# ACB-Lite_3_2.net
KiCad netlist of a schematic drawn in EAGLE
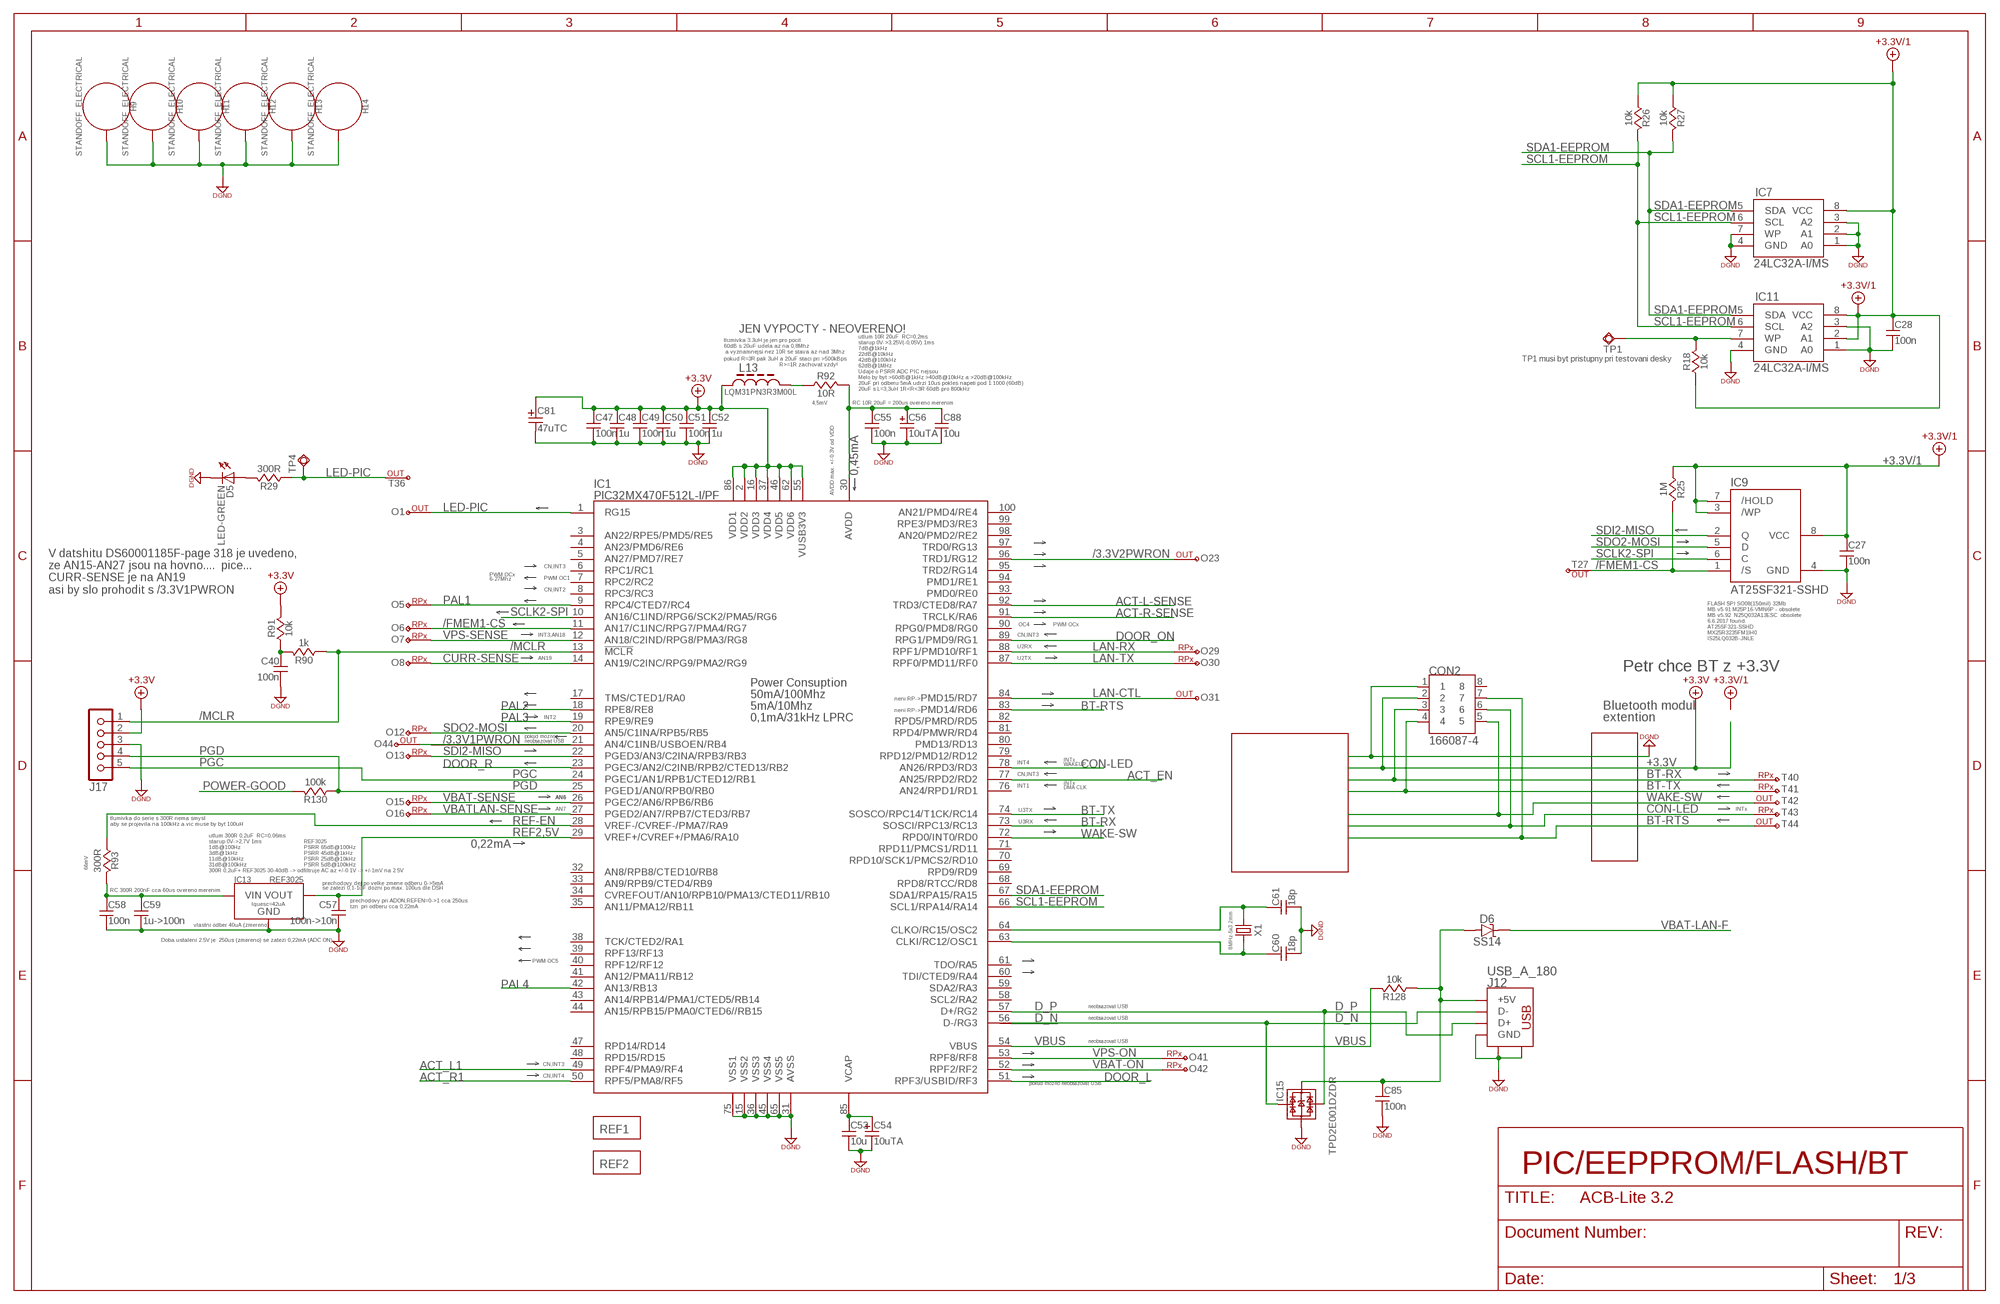
[diagram p0: schematic, sheet 1]
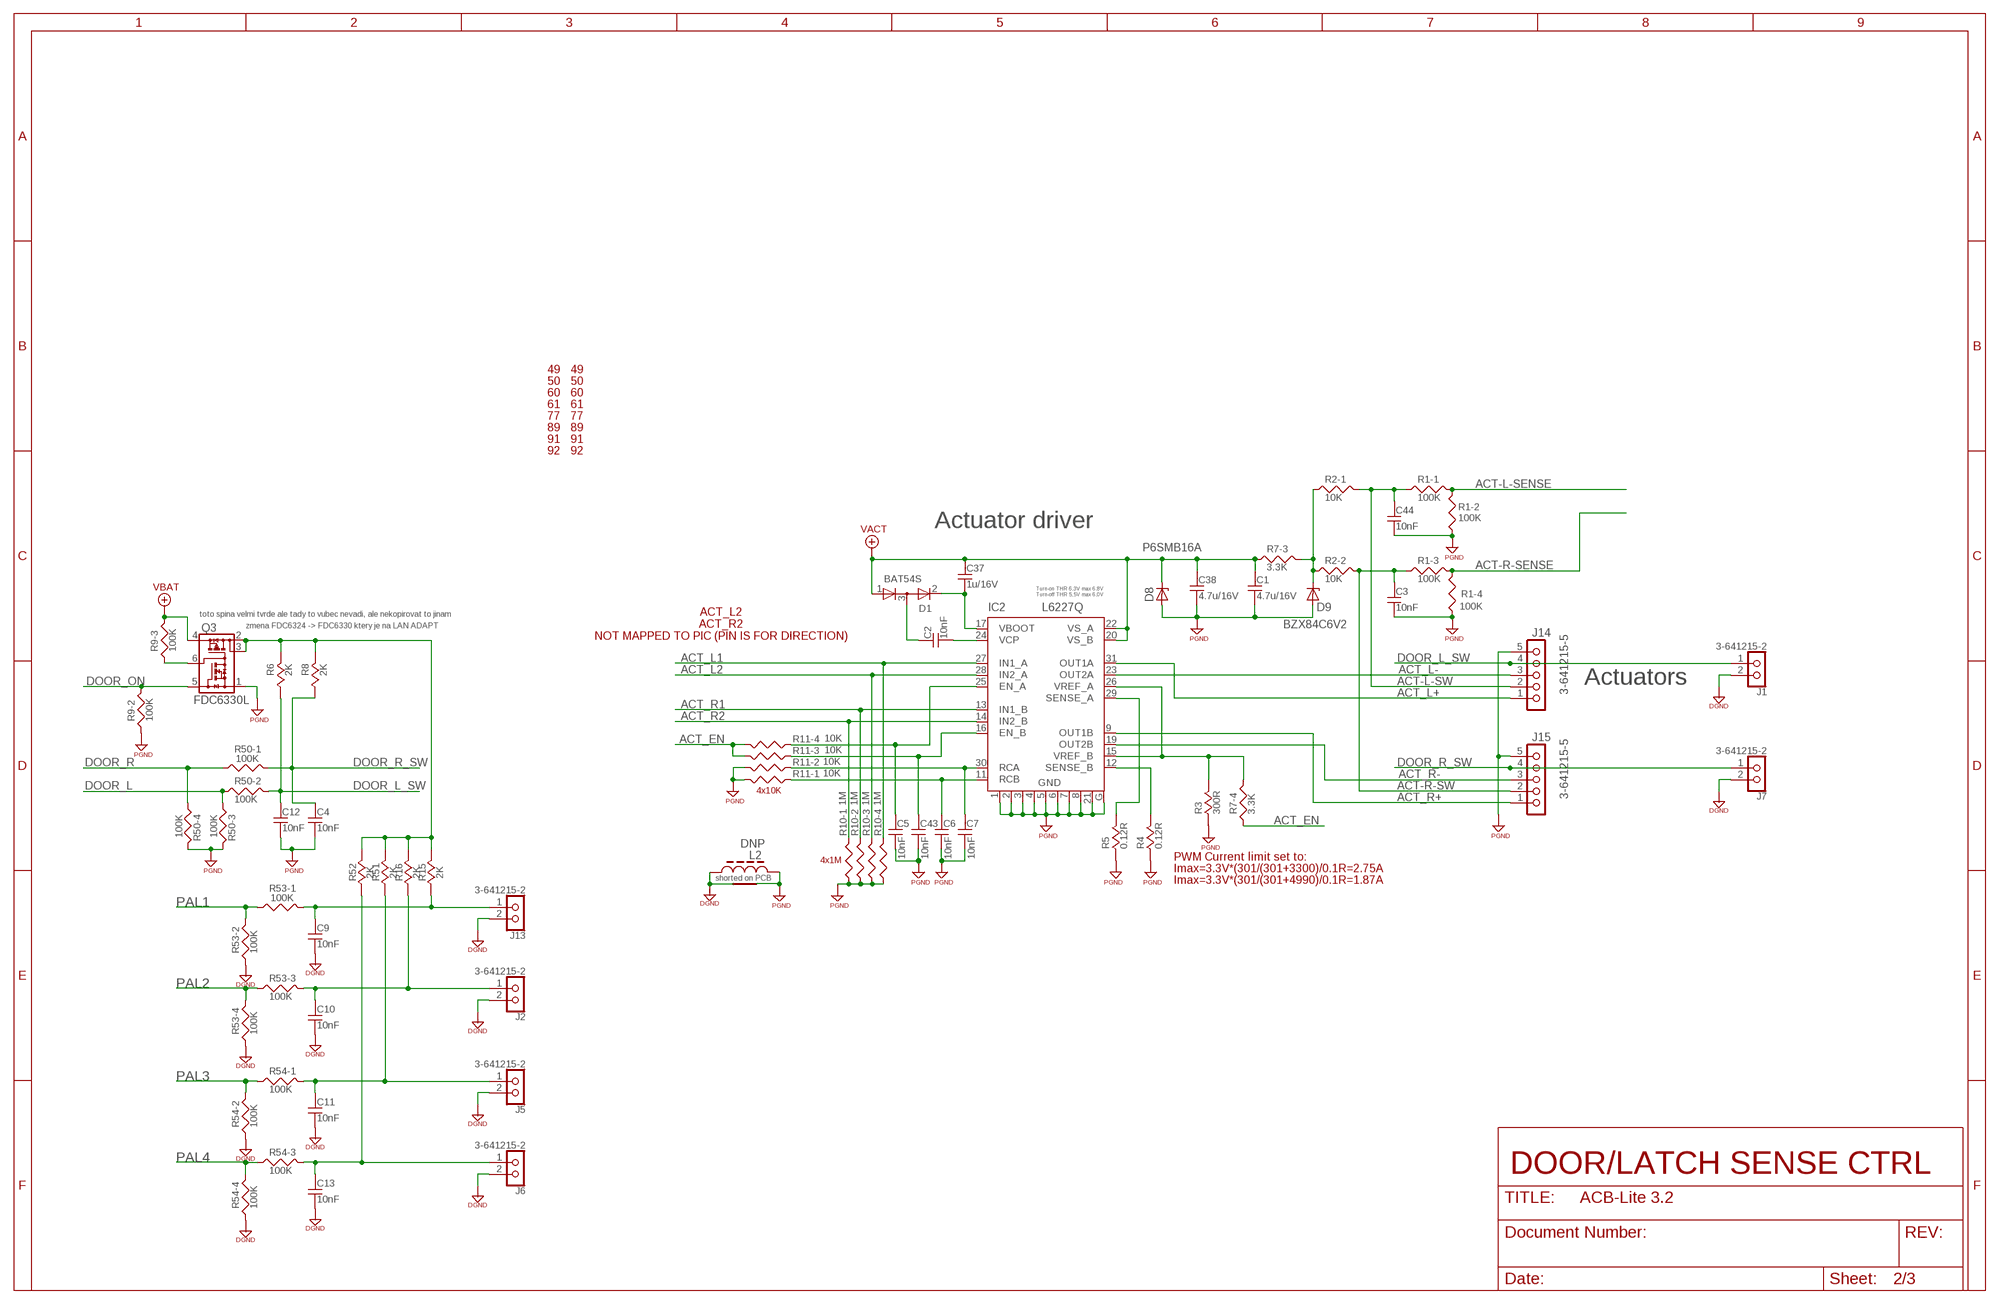
[diagram p1: schematic, sheet 2]
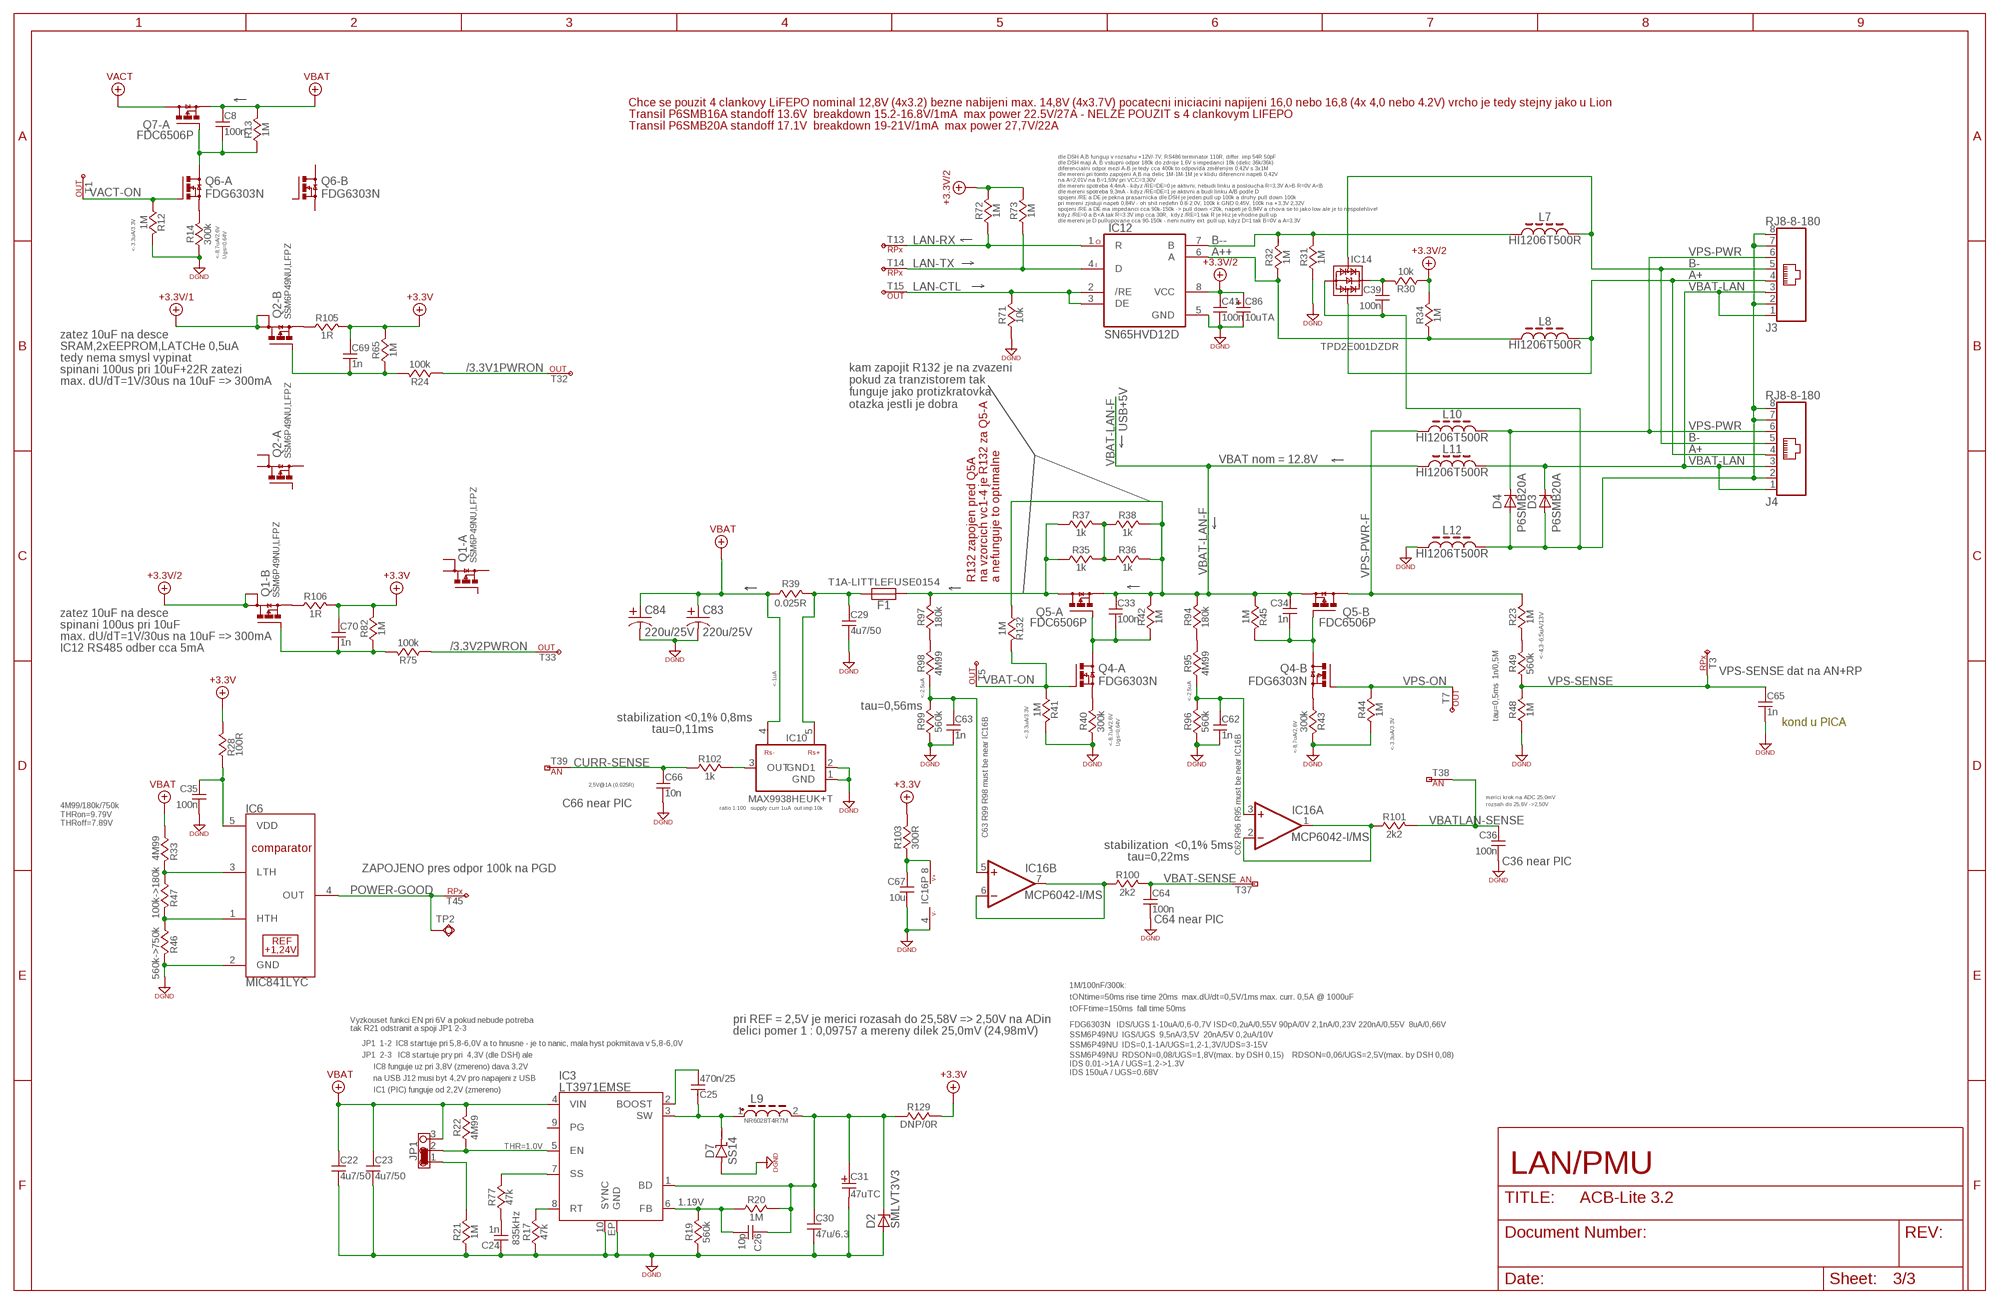
[diagram p2: schematic, sheet 3]

(export (version "E")
  (design (tool "Eeschema 10.0.6"))
  (components
    (comp (ref "C8")
      (value "100n")
      (footprint "eagle-import:0603")
      (libsource (lib "eagle-import") (part "C-0603"))
    )
    (comp (ref "C22")
      (value "4u7/50")
      (footprint "eagle-import:1206")
      (libsource (lib "eagle-import") (part "C-1206"))
    )
    (comp (ref "C23")
      (value "4u7/50")
      (footprint "eagle-import:1206")
      (libsource (lib "eagle-import") (part "C-1206"))
    )
    (comp (ref "C24")
      (value "1n")
      (footprint "eagle-import:0603")
      (libsource (lib "eagle-import") (part "C-0603"))
    )
    (comp (ref "C25")
      (value "470n/25")
      (footprint "eagle-import:0603")
      (libsource (lib "eagle-import") (part "C-0603"))
    )
    (comp (ref "C26")
      (value "10p")
      (footprint "eagle-import:0603")
      (libsource (lib "eagle-import") (part "C-0603"))
    )
    (comp (ref "C29")
      (value "4u7/50")
      (footprint "eagle-import:1206")
      (libsource (lib "eagle-import") (part "C-1206"))
    )
    (comp (ref "C30")
      (value "47u/6.3")
      (footprint "eagle-import:1206")
      (libsource (lib "eagle-import") (part "C-1206"))
    )
    (comp (ref "C31")
      (value "47uTC")
      (footprint "eagle-import:CT-C")
      (libsource (lib "eagle-import") (part "CT-C"))
    )
    (comp (ref "C33")
      (value "100n")
      (footprint "eagle-import:0603")
      (libsource (lib "eagle-import") (part "C-0603"))
    )
    (comp (ref "C34")
      (value "1n")
      (footprint "eagle-import:0603")
      (libsource (lib "eagle-import") (part "C-0603"))
    )
    (comp (ref "C35")
      (value "100n")
      (footprint "eagle-import:0603")
      (libsource (lib "eagle-import") (part "C-0603"))
    )
    (comp (ref "C36")
      (value "100n")
      (footprint "eagle-import:0603")
      (libsource (lib "eagle-import") (part "C-0603"))
    )
    (comp (ref "C39")
      (value "100n")
      (footprint "eagle-import:0603")
      (libsource (lib "eagle-import") (part "C-0603"))
    )
    (comp (ref "C41")
      (value "100n")
      (footprint "eagle-import:0603")
      (libsource (lib "eagle-import") (part "C-0603"))
    )
    (comp (ref "C62")
      (value "1n")
      (footprint "eagle-import:0603")
      (libsource (lib "eagle-import") (part "C-0603"))
    )
    (comp (ref "C63")
      (value "1n")
      (footprint "eagle-import:0603")
      (libsource (lib "eagle-import") (part "C-0603"))
    )
    (comp (ref "C64")
      (value "100n")
      (footprint "eagle-import:0603")
      (libsource (lib "eagle-import") (part "C-0603"))
    )
    (comp (ref "C65")
      (value "1n")
      (footprint "eagle-import:0603")
      (libsource (lib "eagle-import") (part "C-0603"))
    )
    (comp (ref "C66")
      (value "10n")
      (footprint "eagle-import:0603")
      (libsource (lib "eagle-import") (part "C-0603"))
    )
    (comp (ref "C67")
      (value "10u")
      (footprint "eagle-import:0603")
      (libsource (lib "eagle-import") (part "C-0603"))
    )
    (comp (ref "C69")
      (value "1n")
      (footprint "eagle-import:0603")
      (libsource (lib "eagle-import") (part "C-0603"))
    )
    (comp (ref "C70")
      (value "1n")
      (footprint "eagle-import:0603")
      (libsource (lib "eagle-import") (part "C-0603"))
    )
    (comp (ref "C83")
      (value "220u/25V")
      (footprint "eagle-import:CAP_8MM_DIA_SMT")
      (libsource (lib "eagle-import") (part "CAP-ELEC-SMD-8MM"))
    )
    (comp (ref "C84")
      (value "220u/25V")
      (footprint "eagle-import:CAP_8MM_DIA_SMT")
      (libsource (lib "eagle-import") (part "CAP-ELEC-SMD-8MM"))
    )
    (comp (ref "C86")
      (value "10uTA")
      (footprint "eagle-import:1206-POL-C")
      (libsource (lib "eagle-import") (part "CT-1206"))
    )
    (comp (ref "D2")
      (value "SMLVT3V3")
      (footprint "eagle-import:SMA")
      (libsource (lib "eagle-import") (part "SMLVT3V3"))
    )
    (comp (ref "D3")
      (value "P6SMB20A")
      (footprint "eagle-import:SMB")
      (libsource (lib "eagle-import") (part "P6SMB"))
    )
    (comp (ref "D4")
      (value "P6SMB20A")
      (footprint "eagle-import:SMB")
      (libsource (lib "eagle-import") (part "P6SMB"))
    )
    (comp (ref "D7")
      (value "SS14")
      (footprint "eagle-import:SMA")
      (libsource (lib "eagle-import") (part "DS-SMA"))
    )
    (comp (ref "F1")
      (value "T1A-LITTLEFUSE0154")
      (footprint "eagle-import:LITTLEFUSE0154")
      (libsource (lib "eagle-import") (part "POJISTKA-LITTLEFUSE0154"))
    )
    (comp (ref "IC3")
      (value "LT3971EMSE")
      (footprint "eagle-import:MSOP10EXP")
      (libsource (lib "eagle-import") (part "LT3971EMSE"))
    )
    (comp (ref "IC6")
      (value "MIC841LYC")
      (footprint "eagle-import:SC-70-5")
      (libsource (lib "eagle-import") (part "MIC841LYC"))
    )
    (comp (ref "IC10")
      (value "MAX9938HEUK+T")
      (footprint "eagle-import:SOT23-5")
      (libsource (lib "eagle-import") (part "TSM9938HEUK+T"))
    )
    (comp (ref "IC12")
      (value "SN65HVD12D")
      (footprint "eagle-import:SO08")
      (libsource (lib "eagle-import") (part "SN65HVD3082ED"))
    )
    (comp (ref "IC14")
      (value "TPD2E001DZDR")
      (footprint "eagle-import:SOT-143")
      (libsource (lib "eagle-import") (part "SR05.TCT"))
    )
    (comp (ref "IC16")
      (value "MCP6042-I/MS")
      (footprint "eagle-import:MSOP-08")
      (libsource (lib "eagle-import") (part "MCP6042-I/MS"))
    )
    (comp (ref "J3")
      (value "RJ8-8-180")
      (footprint "eagle-import:RJ8-8-180")
      (libsource (lib "eagle-import") (part "RJ8-8-180"))
    )
    (comp (ref "J4")
      (value "RJ8-8-180")
      (footprint "eagle-import:RJ8-8-180")
      (libsource (lib "eagle-import") (part "RJ8-8-180"))
    )
    (comp (ref "JP1")
      (value "JP3CLOSE12")
      (footprint "eagle-import:JP3CLOSE12")
      (libsource (lib "eagle-import") (part "JP3CLOSE12"))
    )
    (comp (ref "L7")
      (value "HI1206T500R")
      (footprint "eagle-import:1206")
      (libsource (lib "eagle-import") (part "L-1206"))
    )
    (comp (ref "L8")
      (value "HI1206T500R")
      (footprint "eagle-import:1206")
      (libsource (lib "eagle-import") (part "L-1206"))
    )
    (comp (ref "L9")
      (value "NR6028T4R7M")
      (footprint "eagle-import:NR6028")
      (libsource (lib "eagle-import") (part "NR6028"))
    )
    (comp (ref "L10")
      (value "HI1206T500R")
      (footprint "eagle-import:1206")
      (libsource (lib "eagle-import") (part "L-1206"))
    )
    (comp (ref "L11")
      (value "HI1206T500R")
      (footprint "eagle-import:1206")
      (libsource (lib "eagle-import") (part "L-1206"))
    )
    (comp (ref "L12")
      (value "HI1206T500R")
      (footprint "eagle-import:1206")
      (libsource (lib "eagle-import") (part "L-1206"))
    )
    (comp (ref "Q1")
      (value "SSM6P49NU,LFPZ")
      (footprint "eagle-import:MICRO_FET")
      (libsource (lib "eagle-import") (part "SSM6P49PZNU,LF"))
    )
    (comp (ref "Q2")
      (value "SSM6P49NU,LFPZ")
      (footprint "eagle-import:MICRO_FET")
      (libsource (lib "eagle-import") (part "SSM6P49PZNU,LF"))
    )
    (comp (ref "Q4")
      (value "FDG6303N")
      (footprint "eagle-import:SC70-6")
      (libsource (lib "eagle-import") (part "FDG6303N"))
    )
    (comp (ref "Q5")
      (value "FDC6506P")
      (footprint "eagle-import:SSOT-6")
      (libsource (lib "eagle-import") (part "FDC6506D"))
    )
    (comp (ref "Q6")
      (value "FDG6303N")
      (footprint "eagle-import:SC70-6")
      (libsource (lib "eagle-import") (part "FDG6303N"))
    )
    (comp (ref "Q7")
      (value "FDC6506P")
      (footprint "eagle-import:SSOT-6")
      (libsource (lib "eagle-import") (part "FDC6506D"))
    )
    (comp (ref "R12")
      (value "1M")
      (footprint "eagle-import:0603")
      (libsource (lib "eagle-import") (part "R-0603"))
    )
    (comp (ref "R13")
      (value "1M")
      (footprint "eagle-import:0603")
      (libsource (lib "eagle-import") (part "R-0603"))
    )
    (comp (ref "R14")
      (value "300k")
      (footprint "eagle-import:0603")
      (libsource (lib "eagle-import") (part "R-0603"))
    )
    (comp (ref "R17")
      (value "47k")
      (footprint "eagle-import:0603")
      (libsource (lib "eagle-import") (part "R-0603"))
    )
    (comp (ref "R19")
      (value "560k")
      (footprint "eagle-import:0603")
      (libsource (lib "eagle-import") (part "R-0603"))
    )
    (comp (ref "R20")
      (value "1M")
      (footprint "eagle-import:0603")
      (libsource (lib "eagle-import") (part "R-0603"))
    )
    (comp (ref "R21")
      (value "1M")
      (footprint "eagle-import:0603")
      (libsource (lib "eagle-import") (part "R-0603"))
    )
    (comp (ref "R22")
      (value "4M99")
      (footprint "eagle-import:0603")
      (libsource (lib "eagle-import") (part "R-0603"))
    )
    (comp (ref "R23")
      (value "1M")
      (footprint "eagle-import:0603")
      (libsource (lib "eagle-import") (part "R-0603"))
    )
    (comp (ref "R24")
      (value "100k")
      (footprint "eagle-import:0603")
      (libsource (lib "eagle-import") (part "R-0603"))
    )
    (comp (ref "R28")
      (value "100R")
      (footprint "eagle-import:0603")
      (libsource (lib "eagle-import") (part "R-0603"))
    )
    (comp (ref "R30")
      (value "10k")
      (footprint "eagle-import:0603")
      (libsource (lib "eagle-import") (part "R-0603"))
    )
    (comp (ref "R31")
      (value "1M")
      (footprint "eagle-import:0603")
      (libsource (lib "eagle-import") (part "R-0603"))
    )
    (comp (ref "R32")
      (value "1M")
      (footprint "eagle-import:0603")
      (libsource (lib "eagle-import") (part "R-0603"))
    )
    (comp (ref "R33")
      (value "4M99")
      (footprint "eagle-import:0603")
      (libsource (lib "eagle-import") (part "R-0603"))
    )
    (comp (ref "R34")
      (value "1M")
      (footprint "eagle-import:0603")
      (libsource (lib "eagle-import") (part "R-0603"))
    )
    (comp (ref "R35")
      (value "1k")
      (footprint "eagle-import:0805")
      (libsource (lib "eagle-import") (part "R-0805"))
    )
    (comp (ref "R36")
      (value "1k")
      (footprint "eagle-import:0805")
      (libsource (lib "eagle-import") (part "R-0805"))
    )
    (comp (ref "R37")
      (value "1k")
      (footprint "eagle-import:0805")
      (libsource (lib "eagle-import") (part "R-0805"))
    )
    (comp (ref "R38")
      (value "1k")
      (footprint "eagle-import:0805")
      (libsource (lib "eagle-import") (part "R-0805"))
    )
    (comp (ref "R39")
      (value "0.025R")
      (footprint "eagle-import:0805")
      (libsource (lib "eagle-import") (part "R-0805"))
    )
    (comp (ref "R40")
      (value "300k")
      (footprint "eagle-import:0603")
      (libsource (lib "eagle-import") (part "R-0603"))
    )
    (comp (ref "R41")
      (value "1M")
      (footprint "eagle-import:0603")
      (libsource (lib "eagle-import") (part "R-0603"))
    )
    (comp (ref "R42")
      (value "1M")
      (footprint "eagle-import:0603")
      (libsource (lib "eagle-import") (part "R-0603"))
    )
    (comp (ref "R43")
      (value "300k")
      (footprint "eagle-import:0603")
      (libsource (lib "eagle-import") (part "R-0603"))
    )
    (comp (ref "R44")
      (value "1M")
      (footprint "eagle-import:0603")
      (libsource (lib "eagle-import") (part "R-0603"))
    )
    (comp (ref "R45")
      (value "1M")
      (footprint "eagle-import:0603")
      (libsource (lib "eagle-import") (part "R-0603"))
    )
    (comp (ref "R46")
      (value "560k->750k")
      (footprint "eagle-import:0603")
      (libsource (lib "eagle-import") (part "R-0603"))
    )
    (comp (ref "R47")
      (value "100k->180k")
      (footprint "eagle-import:0603")
      (libsource (lib "eagle-import") (part "R-0603"))
    )
    (comp (ref "R48")
      (value "1M")
      (footprint "eagle-import:0603")
      (libsource (lib "eagle-import") (part "R-0603"))
    )
    (comp (ref "R49")
      (value "560k")
      (footprint "eagle-import:0603")
      (libsource (lib "eagle-import") (part "R-0603"))
    )
    (comp (ref "R65")
      (value "1M")
      (footprint "eagle-import:0603")
      (libsource (lib "eagle-import") (part "R-0603"))
    )
    (comp (ref "R71")
      (value "10k")
      (footprint "eagle-import:0603")
      (libsource (lib "eagle-import") (part "R-0603"))
    )
    (comp (ref "R72")
      (value "1M")
      (footprint "eagle-import:0603")
      (libsource (lib "eagle-import") (part "R-0603"))
    )
    (comp (ref "R73")
      (value "1M")
      (footprint "eagle-import:0603")
      (libsource (lib "eagle-import") (part "R-0603"))
    )
    (comp (ref "R75")
      (value "100k")
      (footprint "eagle-import:0603")
      (libsource (lib "eagle-import") (part "R-0603"))
    )
    (comp (ref "R77")
      (value "47k")
      (footprint "eagle-import:0603")
      (libsource (lib "eagle-import") (part "R-0603"))
    )
    (comp (ref "R82")
      (value "1M")
      (footprint "eagle-import:0603")
      (libsource (lib "eagle-import") (part "R-0603"))
    )
    (comp (ref "R94")
      (value "180k")
      (footprint "eagle-import:0603")
      (libsource (lib "eagle-import") (part "R-0603"))
    )
    (comp (ref "R95")
      (value "4M99")
      (footprint "eagle-import:0603")
      (libsource (lib "eagle-import") (part "R-0603"))
    )
    (comp (ref "R96")
      (value "560k")
      (footprint "eagle-import:0603")
      (libsource (lib "eagle-import") (part "R-0603"))
    )
    (comp (ref "R97")
      (value "180k")
      (footprint "eagle-import:0603")
      (libsource (lib "eagle-import") (part "R-0603"))
    )
    (comp (ref "R98")
      (value "4M99")
      (footprint "eagle-import:0603")
      (libsource (lib "eagle-import") (part "R-0603"))
    )
    (comp (ref "R99")
      (value "560k")
      (footprint "eagle-import:0603")
      (libsource (lib "eagle-import") (part "R-0603"))
    )
    (comp (ref "R100")
      (value "2k2")
      (footprint "eagle-import:0603")
      (libsource (lib "eagle-import") (part "R-0603"))
    )
    (comp (ref "R101")
      (value "2k2")
      (footprint "eagle-import:0603")
      (libsource (lib "eagle-import") (part "R-0603"))
    )
    (comp (ref "R102")
      (value "1k")
      (footprint "eagle-import:0603")
      (libsource (lib "eagle-import") (part "R-0603"))
    )
    (comp (ref "R103")
      (value "300R")
      (footprint "eagle-import:0603")
      (libsource (lib "eagle-import") (part "R-0603"))
    )
    (comp (ref "R105")
      (value "1R")
      (footprint "eagle-import:0805")
      (libsource (lib "eagle-import") (part "R-0805"))
    )
    (comp (ref "R106")
      (value "1R")
      (footprint "eagle-import:0805")
      (libsource (lib "eagle-import") (part "R-0805"))
    )
    (comp (ref "R129")
      (value "DNP/0R")
      (footprint "eagle-import:0603")
      (libsource (lib "eagle-import") (part "R-0603"))
    )
    (comp (ref "R132")
      (value "1M")
      (footprint "eagle-import:0603")
      (libsource (lib "eagle-import") (part "R-0603"))
    )
    (comp (ref "T1")
      (value "PIC-OUT")
      (footprint "eagle-import:TEMP-PAD")
      (libsource (lib "eagle-import") (part "PIC-OUT"))
    )
    (comp (ref "T3")
      (value "PIC-RPX")
      (footprint "eagle-import:TEMP-PAD")
      (libsource (lib "eagle-import") (part "PIC-RPX"))
    )
    (comp (ref "T5")
      (value "PIC-OUT")
      (footprint "eagle-import:TEMP-PAD")
      (libsource (lib "eagle-import") (part "PIC-OUT"))
    )
    (comp (ref "T7")
      (value "PIC-OUT")
      (footprint "eagle-import:TEMP-PAD")
      (libsource (lib "eagle-import") (part "PIC-OUT"))
    )
    (comp (ref "T13")
      (value "PIC-RPX")
      (footprint "eagle-import:TEMP-PAD")
      (libsource (lib "eagle-import") (part "PIC-RPX"))
    )
    (comp (ref "T14")
      (value "PIC-RPX")
      (footprint "eagle-import:TEMP-PAD")
      (libsource (lib "eagle-import") (part "PIC-RPX"))
    )
    (comp (ref "T15")
      (value "PIC-OUT")
      (footprint "eagle-import:TEMP-PAD")
      (libsource (lib "eagle-import") (part "PIC-OUT"))
    )
    (comp (ref "T32")
      (value "PIC-OUT")
      (footprint "eagle-import:TEMP-PAD")
      (libsource (lib "eagle-import") (part "PIC-OUT"))
    )
    (comp (ref "T33")
      (value "PIC-OUT")
      (footprint "eagle-import:TEMP-PAD")
      (libsource (lib "eagle-import") (part "PIC-OUT"))
    )
    (comp (ref "T37")
      (value "PIN-AN")
      (footprint "eagle-import:TEMP-PAD")
      (libsource (lib "eagle-import") (part "PIN-AN"))
    )
    (comp (ref "T38")
      (value "PIN-AN")
      (footprint "eagle-import:TEMP-PAD")
      (libsource (lib "eagle-import") (part "PIN-AN"))
    )
    (comp (ref "T39")
      (value "PIN-AN")
      (footprint "eagle-import:TEMP-PAD")
      (libsource (lib "eagle-import") (part "PIN-AN"))
    )
    (comp (ref "T45")
      (value "PIC-RPX")
      (footprint "eagle-import:TEMP-PAD")
      (libsource (lib "eagle-import") (part "PIC-RPX"))
    )
    (comp (ref "TP2")
      (value "DNP-TestPoint")
      (footprint "eagle-import:TH_ROUND_14MM08MM")
      (libsource (lib "eagle-import") (part "ROUND_SMDTH1.4MM"))
    )
    (comp (ref "C1")
      (value "4.7u/16V")
      (footprint "eagle-import:0805")
      (libsource (lib "eagle-import") (part "C-0805"))
    )
    (comp (ref "C2")
      (value "10nF")
      (footprint "eagle-import:0603")
      (libsource (lib "eagle-import") (part "C-0603"))
    )
    (comp (ref "C3")
      (value "10nF")
      (footprint "eagle-import:0603")
      (libsource (lib "eagle-import") (part "C-0603"))
    )
    (comp (ref "C4")
      (value "10nF")
      (footprint "eagle-import:0603")
      (libsource (lib "eagle-import") (part "C-0603"))
    )
    (comp (ref "C5")
      (value "10nF")
      (footprint "eagle-import:0603")
      (libsource (lib "eagle-import") (part "C-0603"))
    )
    (comp (ref "C6")
      (value "10nF")
      (footprint "eagle-import:0603")
      (libsource (lib "eagle-import") (part "C-0603"))
    )
    (comp (ref "C7")
      (value "10nF")
      (footprint "eagle-import:0603")
      (libsource (lib "eagle-import") (part "C-0603"))
    )
    (comp (ref "C9")
      (value "10nF")
      (footprint "eagle-import:0603")
      (libsource (lib "eagle-import") (part "C-0603"))
    )
    (comp (ref "C10")
      (value "10nF")
      (footprint "eagle-import:0603")
      (libsource (lib "eagle-import") (part "C-0603"))
    )
    (comp (ref "C11")
      (value "10nF")
      (footprint "eagle-import:0603")
      (libsource (lib "eagle-import") (part "C-0603"))
    )
    (comp (ref "C12")
      (value "10nF")
      (footprint "eagle-import:0603")
      (libsource (lib "eagle-import") (part "C-0603"))
    )
    (comp (ref "C13")
      (value "10nF")
      (footprint "eagle-import:0603")
      (libsource (lib "eagle-import") (part "C-0603"))
    )
    (comp (ref "C37")
      (value "1u/16V")
      (footprint "eagle-import:0603")
      (libsource (lib "eagle-import") (part "C-0603"))
    )
    (comp (ref "C38")
      (value "4.7u/16V")
      (footprint "eagle-import:0805")
      (libsource (lib "eagle-import") (part "C-0805"))
    )
    (comp (ref "C43")
      (value "10nF")
      (footprint "eagle-import:0603")
      (libsource (lib "eagle-import") (part "C-0603"))
    )
    (comp (ref "C44")
      (value "10nF")
      (footprint "eagle-import:0603")
      (libsource (lib "eagle-import") (part "C-0603"))
    )
    (comp (ref "D1")
      (value "BAT54S")
      (footprint "eagle-import:SOT-23")
      (libsource (lib "eagle-import") (part "BAT54S"))
    )
    (comp (ref "D8")
      (value "P6SMB16A")
      (footprint "eagle-import:SMB")
      (libsource (lib "eagle-import") (part "P6SMB"))
    )
    (comp (ref "D9")
      (value "BZX84C6V2")
      (footprint "eagle-import:SOT-23")
      (libsource (lib "eagle-import") (part "BZX84C6V2"))
    )
    (comp (ref "IC2")
      (value "L6227Q")
      (footprint "eagle-import:SQFP-S-5X5-32")
      (libsource (lib "eagle-import") (part "L6227Q"))
    )
    (comp (ref "J1")
      (value "3-641215-2")
      (footprint "eagle-import:3-641215-2")
      (libsource (lib "eagle-import") (part "3-641215-2"))
    )
    (comp (ref "J2")
      (value "3-641215-2")
      (footprint "eagle-import:3-641215-2")
      (libsource (lib "eagle-import") (part "3-641215-2"))
    )
    (comp (ref "J5")
      (value "3-641215-2")
      (footprint "eagle-import:3-641215-2")
      (libsource (lib "eagle-import") (part "3-641215-2"))
    )
    (comp (ref "J6")
      (value "3-641215-2")
      (footprint "eagle-import:3-641215-2")
      (libsource (lib "eagle-import") (part "3-641215-2"))
    )
    (comp (ref "J7")
      (value "3-641215-2")
      (footprint "eagle-import:3-641215-2")
      (libsource (lib "eagle-import") (part "3-641215-2"))
    )
    (comp (ref "J13")
      (value "3-641215-2")
      (footprint "eagle-import:3-641215-2")
      (libsource (lib "eagle-import") (part "3-641215-2"))
    )
    (comp (ref "J14")
      (value "3-641215-5")
      (footprint "eagle-import:3-641215-5")
      (libsource (lib "eagle-import") (part "3-641215-5"))
    )
    (comp (ref "J15")
      (value "3-641215-5")
      (footprint "eagle-import:3-641215-5")
      (libsource (lib "eagle-import") (part "3-641215-5"))
    )
    (comp (ref "L2")
      (value "DNP")
      (footprint "eagle-import:0805-0RTOP")
      (libsource (lib "eagle-import") (part "L-0805-0R"))
    )
    (comp (ref "Q3")
      (value "FDC6330L")
      (footprint "eagle-import:SSOT-6")
      (libsource (lib "eagle-import") (part "FDC6330L"))
    )
    (comp (ref "R1")
      (value "100K")
      (footprint "eagle-import:0603-ARRAY")
      (libsource (lib "eagle-import") (part "EXB-38"))
    )
    (comp (ref "R2")
      (value "10K")
      (footprint "eagle-import:0603-ARRAY")
      (libsource (lib "eagle-import") (part "EXB-38"))
    )
    (comp (ref "R3")
      (value "300R")
      (footprint "eagle-import:0603")
      (libsource (lib "eagle-import") (part "R-0603"))
    )
    (comp (ref "R4")
      (value "0.12R")
      (footprint "eagle-import:0805")
      (libsource (lib "eagle-import") (part "R-0805"))
    )
    (comp (ref "R5")
      (value "0.12R")
      (footprint "eagle-import:0805")
      (libsource (lib "eagle-import") (part "R-0805"))
    )
    (comp (ref "R6")
      (value "2K")
      (footprint "eagle-import:0603")
      (libsource (lib "eagle-import") (part "R-0603"))
    )
    (comp (ref "R7")
      (value "3.3K")
      (footprint "eagle-import:0603-ARRAY")
      (libsource (lib "eagle-import") (part "EXB-38"))
    )
    (comp (ref "R8")
      (value "2K")
      (footprint "eagle-import:0603")
      (libsource (lib "eagle-import") (part "R-0603"))
    )
    (comp (ref "R9")
      (value "100K")
      (footprint "eagle-import:0603-ARRAY")
      (libsource (lib "eagle-import") (part "EXB-38"))
    )
    (comp (ref "R10")
      (value "1M")
      (footprint "eagle-import:0603-ARRAY")
      (libsource (lib "eagle-import") (part "EXB-38"))
    )
    (comp (ref "R11")
      (value "10K")
      (footprint "eagle-import:0603-ARRAY")
      (libsource (lib "eagle-import") (part "EXB-38"))
    )
    (comp (ref "R15")
      (value "2K")
      (footprint "eagle-import:0603")
      (libsource (lib "eagle-import") (part "R-0603"))
    )
    (comp (ref "R16")
      (value "2K")
      (footprint "eagle-import:0603")
      (libsource (lib "eagle-import") (part "R-0603"))
    )
    (comp (ref "R50")
      (value "100K")
      (footprint "eagle-import:0603-ARRAY")
      (libsource (lib "eagle-import") (part "EXB-38"))
    )
    (comp (ref "R51")
      (value "2K")
      (footprint "eagle-import:0603")
      (libsource (lib "eagle-import") (part "R-0603"))
    )
    (comp (ref "R52")
      (value "2K")
      (footprint "eagle-import:0603")
      (libsource (lib "eagle-import") (part "R-0603"))
    )
    (comp (ref "R53")
      (value "100K")
      (footprint "eagle-import:0603-ARRAY")
      (libsource (lib "eagle-import") (part "EXB-38"))
    )
    (comp (ref "R54")
      (value "100K")
      (footprint "eagle-import:0603-ARRAY")
      (libsource (lib "eagle-import") (part "EXB-38"))
    )
    (comp (ref "C27")
      (value "100n")
      (footprint "eagle-import:0603")
      (libsource (lib "eagle-import") (part "C-0603"))
    )
    (comp (ref "C28")
      (value "100n")
      (footprint "eagle-import:0603")
      (libsource (lib "eagle-import") (part "C-0603"))
    )
    (comp (ref "C40")
      (value "100n")
      (footprint "eagle-import:0603")
      (libsource (lib "eagle-import") (part "C-0603"))
    )
    (comp (ref "C47")
      (value "100n")
      (footprint "eagle-import:0603")
      (libsource (lib "eagle-import") (part "C-0603"))
    )
    (comp (ref "C48")
      (value "1u")
      (footprint "eagle-import:0603")
      (libsource (lib "eagle-import") (part "C-0603"))
    )
    (comp (ref "C49")
      (value "100n")
      (footprint "eagle-import:0603")
      (libsource (lib "eagle-import") (part "C-0603"))
    )
    (comp (ref "C50")
      (value "1u")
      (footprint "eagle-import:0603")
      (libsource (lib "eagle-import") (part "C-0603"))
    )
    (comp (ref "C51")
      (value "100n")
      (footprint "eagle-import:0603")
      (libsource (lib "eagle-import") (part "C-0603"))
    )
    (comp (ref "C52")
      (value "1u")
      (footprint "eagle-import:0603")
      (libsource (lib "eagle-import") (part "C-0603"))
    )
    (comp (ref "C53")
      (value "10u")
      (footprint "eagle-import:0603")
      (libsource (lib "eagle-import") (part "C-0603"))
    )
    (comp (ref "C54")
      (value "10uTA")
      (footprint "eagle-import:1206-POL-C")
      (libsource (lib "eagle-import") (part "CT-1206"))
    )
    (comp (ref "C55")
      (value "100n")
      (footprint "eagle-import:0603")
      (libsource (lib "eagle-import") (part "C-0603"))
    )
    (comp (ref "C56")
      (value "10uTA")
      (footprint "eagle-import:1206-POL-C")
      (libsource (lib "eagle-import") (part "CT-1206"))
    )
    (comp (ref "C57")
      (value "100n->10n")
      (footprint "eagle-import:0603")
      (libsource (lib "eagle-import") (part "C-0603"))
    )
    (comp (ref "C58")
      (value "100n")
      (footprint "eagle-import:0603")
      (libsource (lib "eagle-import") (part "C-0603"))
    )
    (comp (ref "C59")
      (value "1u->100n")
      (footprint "eagle-import:0603")
      (libsource (lib "eagle-import") (part "C-0603"))
    )
    (comp (ref "C60")
      (value "18p")
      (footprint "eagle-import:0603")
      (libsource (lib "eagle-import") (part "C-0603"))
    )
    (comp (ref "C61")
      (value "18p")
      (footprint "eagle-import:0603")
      (libsource (lib "eagle-import") (part "C-0603"))
    )
    (comp (ref "C81")
      (value "47uTC")
      (footprint "eagle-import:CT-C")
      (libsource (lib "eagle-import") (part "CT-C"))
    )
    (comp (ref "C85")
      (value "100n")
      (footprint "eagle-import:0603")
      (libsource (lib "eagle-import") (part "C-0603"))
    )
    (comp (ref "C88")
      (value "10u")
      (footprint "eagle-import:0603")
      (libsource (lib "eagle-import") (part "C-0603"))
    )
    (comp (ref "CON2")
      (value "166087-4")
      (footprint "eagle-import:166087-4")
      (libsource (lib "eagle-import") (part "166087-4"))
    )
    (comp (ref "D5")
      (value "LED-GREEN")
      (footprint "eagle-import:0805-POL-D")
      (libsource (lib "eagle-import") (part "LED-0805"))
    )
    (comp (ref "D6")
      (value "SS14")
      (footprint "eagle-import:SMA")
      (libsource (lib "eagle-import") (part "DS-SMA"))
    )
    (comp (ref "H9")
      (value "STANDOFF_ELECTRICAL")
      (footprint "eagle-import:STANDOFF-ELECTRICAL")
      (libsource (lib "eagle-import") (part "STANDOFF_ELECTRICAL"))
    )
    (comp (ref "H10")
      (value "STANDOFF_ELECTRICAL")
      (footprint "eagle-import:STANDOFF-ELECTRICAL")
      (libsource (lib "eagle-import") (part "STANDOFF_ELECTRICAL"))
    )
    (comp (ref "H11")
      (value "STANDOFF_ELECTRICAL")
      (footprint "eagle-import:STANDOFF-ELECTRICAL")
      (libsource (lib "eagle-import") (part "STANDOFF_ELECTRICAL"))
    )
    (comp (ref "H12")
      (value "STANDOFF_ELECTRICAL")
      (footprint "eagle-import:STANDOFF-ELECTRICAL")
      (libsource (lib "eagle-import") (part "STANDOFF_ELECTRICAL"))
    )
    (comp (ref "H13")
      (value "STANDOFF_ELECTRICAL")
      (footprint "eagle-import:STANDOFF-ELECTRICAL")
      (libsource (lib "eagle-import") (part "STANDOFF_ELECTRICAL"))
    )
    (comp (ref "H14")
      (value "STANDOFF_ELECTRICAL")
      (footprint "eagle-import:STANDOFF-ELECTRICAL")
      (libsource (lib "eagle-import") (part "STANDOFF_ELECTRICAL"))
    )
    (comp (ref "IC1")
      (value "PIC32MX470F512L-I/PF")
      (footprint "eagle-import:TQFP100_14X14_0,5MM")
      (libsource (lib "eagle-import") (part "PIC32MX470F512L-I/PF"))
    )
    (comp (ref "IC7")
      (value "24LC32A-I/MS")
      (footprint "eagle-import:MSOP-08")
      (libsource (lib "eagle-import") (part "24-I/MS"))
    )
    (comp (ref "IC9")
      (value "AT25SF321-SSHD")
      (footprint "eagle-import:SO-08")
      (libsource (lib "eagle-import") (part "M25P16-VMN6P"))
    )
    (comp (ref "IC11")
      (value "24LC32A-I/MS")
      (footprint "eagle-import:MSOP-08")
      (libsource (lib "eagle-import") (part "24-I/MS"))
    )
    (comp (ref "IC13")
      (value "REF3025")
      (footprint "eagle-import:SOT23")
      (libsource (lib "eagle-import") (part "REF3025"))
    )
    (comp (ref "IC15")
      (value "TPD2E001DZDR")
      (footprint "eagle-import:SOT-143")
      (libsource (lib "eagle-import") (part "SR05.TCT"))
    )
    (comp (ref "J12")
      (value "USB_A_180")
      (footprint "eagle-import:USB_B_180")
      (libsource (lib "eagle-import") (part "USB_B_180"))
    )
    (comp (ref "J17")
      (value "DNP-open-hole")
      (footprint "eagle-import:MA05-1")
      (libsource (lib "eagle-import") (part "MA05-1"))
    )
    (comp (ref "L13")
      (value "LQM31PN3R3M00L")
      (footprint "eagle-import:1206")
      (libsource (lib "eagle-import") (part "L-1206"))
    )
    (comp (ref "O1")
      (value "PIC-OUT")
      (footprint "eagle-import:TEMP-PAD")
      (libsource (lib "eagle-import") (part "PIC-OUT"))
    )
    (comp (ref "O5")
      (value "PIC-RPX")
      (footprint "eagle-import:TEMP-PAD")
      (libsource (lib "eagle-import") (part "PIC-RPX"))
    )
    (comp (ref "O6")
      (value "PIC-RPX")
      (footprint "eagle-import:TEMP-PAD")
      (libsource (lib "eagle-import") (part "PIC-RPX"))
    )
    (comp (ref "O7")
      (value "PIC-RPX")
      (footprint "eagle-import:TEMP-PAD")
      (libsource (lib "eagle-import") (part "PIC-RPX"))
    )
    (comp (ref "O8")
      (value "PIC-RPX")
      (footprint "eagle-import:TEMP-PAD")
      (libsource (lib "eagle-import") (part "PIC-RPX"))
    )
    (comp (ref "O12")
      (value "PIC-RPX")
      (footprint "eagle-import:TEMP-PAD")
      (libsource (lib "eagle-import") (part "PIC-RPX"))
    )
    (comp (ref "O13")
      (value "PIC-RPX")
      (footprint "eagle-import:TEMP-PAD")
      (libsource (lib "eagle-import") (part "PIC-RPX"))
    )
    (comp (ref "O15")
      (value "PIC-RPX")
      (footprint "eagle-import:TEMP-PAD")
      (libsource (lib "eagle-import") (part "PIC-RPX"))
    )
    (comp (ref "O16")
      (value "PIC-RPX")
      (footprint "eagle-import:TEMP-PAD")
      (libsource (lib "eagle-import") (part "PIC-RPX"))
    )
    (comp (ref "O23")
      (value "PIC-OUT")
      (footprint "eagle-import:TEMP-PAD")
      (libsource (lib "eagle-import") (part "PIC-OUT"))
    )
    (comp (ref "O29")
      (value "PIC-RPX")
      (footprint "eagle-import:TEMP-PAD")
      (libsource (lib "eagle-import") (part "PIC-RPX"))
    )
    (comp (ref "O30")
      (value "PIC-RPX")
      (footprint "eagle-import:TEMP-PAD")
      (libsource (lib "eagle-import") (part "PIC-RPX"))
    )
    (comp (ref "O31")
      (value "PIC-OUT")
      (footprint "eagle-import:TEMP-PAD")
      (libsource (lib "eagle-import") (part "PIC-OUT"))
    )
    (comp (ref "O41")
      (value "PIC-RPX")
      (footprint "eagle-import:TEMP-PAD")
      (libsource (lib "eagle-import") (part "PIC-RPX"))
    )
    (comp (ref "O42")
      (value "PIC-RPX")
      (footprint "eagle-import:TEMP-PAD")
      (libsource (lib "eagle-import") (part "PIC-RPX"))
    )
    (comp (ref "O44")
      (value "PIC-OUT")
      (footprint "eagle-import:TEMP-PAD")
      (libsource (lib "eagle-import") (part "PIC-OUT"))
    )
    (comp (ref "R18")
      (value "10k")
      (footprint "eagle-import:0603")
      (libsource (lib "eagle-import") (part "R-0603"))
    )
    (comp (ref "R25")
      (value "1M")
      (footprint "eagle-import:0603")
      (libsource (lib "eagle-import") (part "R-0603"))
    )
    (comp (ref "R26")
      (value "10k")
      (footprint "eagle-import:0603")
      (libsource (lib "eagle-import") (part "R-0603"))
    )
    (comp (ref "R27")
      (value "10k")
      (footprint "eagle-import:0603")
      (libsource (lib "eagle-import") (part "R-0603"))
    )
    (comp (ref "R29")
      (value "300R")
      (footprint "eagle-import:0603")
      (libsource (lib "eagle-import") (part "R-0603"))
    )
    (comp (ref "R90")
      (value "1k")
      (footprint "eagle-import:0603")
      (libsource (lib "eagle-import") (part "R-0603"))
    )
    (comp (ref "R91")
      (value "10k")
      (footprint "eagle-import:0603")
      (libsource (lib "eagle-import") (part "R-0603"))
    )
    (comp (ref "R92")
      (value "10R")
      (footprint "eagle-import:0603")
      (libsource (lib "eagle-import") (part "R-0603"))
    )
    (comp (ref "R93")
      (value "300R")
      (footprint "eagle-import:0603")
      (libsource (lib "eagle-import") (part "R-0603"))
    )
    (comp (ref "R128")
      (value "10k")
      (footprint "eagle-import:0603")
      (libsource (lib "eagle-import") (part "R-0603"))
    )
    (comp (ref "R130")
      (value "100k")
      (footprint "eagle-import:0603")
      (libsource (lib "eagle-import") (part "R-0603"))
    )
    (comp (ref "REF1")
      (value "REF")
      (footprint "eagle-import:REF")
      (libsource (lib "eagle-import") (part "REF"))
    )
    (comp (ref "REF2")
      (value "REF")
      (footprint "eagle-import:REF")
      (libsource (lib "eagle-import") (part "REF"))
    )
    (comp (ref "T27")
      (value "PIC-OUT")
      (footprint "eagle-import:TEMP-PAD")
      (libsource (lib "eagle-import") (part "PIC-OUT"))
    )
    (comp (ref "T36")
      (value "PIC-OUT")
      (footprint "eagle-import:TEMP-PAD")
      (libsource (lib "eagle-import") (part "PIC-OUT"))
    )
    (comp (ref "T40")
      (value "PIC-RPX")
      (footprint "eagle-import:TEMP-PAD")
      (libsource (lib "eagle-import") (part "PIC-RPX"))
    )
    (comp (ref "T41")
      (value "PIC-RPX")
      (footprint "eagle-import:TEMP-PAD")
      (libsource (lib "eagle-import") (part "PIC-RPX"))
    )
    (comp (ref "T42")
      (value "PIC-OUT")
      (footprint "eagle-import:TEMP-PAD")
      (libsource (lib "eagle-import") (part "PIC-OUT"))
    )
    (comp (ref "T43")
      (value "PIC-RPX")
      (footprint "eagle-import:TEMP-PAD")
      (libsource (lib "eagle-import") (part "PIC-RPX"))
    )
    (comp (ref "T44")
      (value "PIC-OUT")
      (footprint "eagle-import:TEMP-PAD")
      (libsource (lib "eagle-import") (part "PIC-OUT"))
    )
    (comp (ref "TP1")
      (value "DNP-TestPoint")
      (footprint "eagle-import:SMD_ROUND_1MM")
      (libsource (lib "eagle-import") (part "ROUND_SMD1MM"))
    )
    (comp (ref "TP4")
      (value "DNP-TestPoint")
      (footprint "eagle-import:TH_ROUND_14MM08MM")
      (libsource (lib "eagle-import") (part "ROUND_SMDTH1.4MM"))
    )
    (comp (ref "X1")
      (value "8MHz-5x3.2mm")
      (footprint "eagle-import:7B")
      (libsource (lib "eagle-import") (part "XTAL-7B"))
    )
  )
  (nets
    (net (code "1") (name "+3.3V") (class "Default")
      (node (ref "C47") (pin "1") (pinfunction "1_1") (pintype "passive"))
      (node (ref "C48") (pin "1") (pinfunction "1_1") (pintype "passive"))
      (node (ref "C49") (pin "1") (pinfunction "1_1") (pintype "passive"))
      (node (ref "C50") (pin "1") (pinfunction "1_1") (pintype "passive"))
      (node (ref "C51") (pin "1") (pinfunction "1_1") (pintype "passive"))
      (node (ref "C52") (pin "1") (pinfunction "1_1") (pintype "passive"))
      (node (ref "C69") (pin "1") (pinfunction "1_1") (pintype "passive"))
      (node (ref "C70") (pin "1") (pinfunction "1_1") (pintype "passive"))
      (node (ref "C81") (pin "+") (pinfunction "+_+") (pintype "passive"))
      (node (ref "CON2") (pin "2") (pinfunction "2_2") (pintype "bidirectional"))
      (node (ref "IC1") (pin "16") (pinfunction "VDD3_16") (pintype "input"))
      (node (ref "IC1") (pin "2") (pinfunction "VDD2_2") (pintype "input"))
      (node (ref "IC1") (pin "37") (pinfunction "VDD4_37") (pintype "input"))
      (node (ref "IC1") (pin "46") (pinfunction "VDD5_46") (pintype "input"))
      (node (ref "IC1") (pin "55") (pinfunction "VUSB3V3_55") (pintype "input"))
      (node (ref "IC1") (pin "62") (pinfunction "VDD6_62") (pintype "input"))
      (node (ref "IC1") (pin "86") (pinfunction "VDD1_86") (pintype "input"))
      (node (ref "J17") (pin "2") (pinfunction "2_2") (pintype "passive"))
      (node (ref "L13") (pin "1") (pinfunction "1_1") (pintype "passive"))
      (node (ref "R103") (pin "2") (pinfunction "2_2") (pintype "passive"))
      (node (ref "R105") (pin "2") (pinfunction "2_2") (pintype "passive"))
      (node (ref "R106") (pin "2") (pinfunction "2_2") (pintype "passive"))
      (node (ref "R129") (pin "1") (pinfunction "1_1") (pintype "passive"))
      (node (ref "R28") (pin "2") (pinfunction "2_2") (pintype "passive"))
      (node (ref "R65") (pin "1") (pinfunction "1_1") (pintype "passive"))
      (node (ref "R82") (pin "1") (pinfunction "1_1") (pintype "passive"))
      (node (ref "R91") (pin "2") (pinfunction "2_2") (pintype "passive"))
    )
    (net (code "2") (name "+3.3V{slash}1") (class "Default")
      (node (ref "C27") (pin "1") (pinfunction "1_1") (pintype "passive"))
      (node (ref "C28") (pin "1") (pinfunction "1_1") (pintype "passive"))
      (node (ref "IC11") (pin "2") (pinfunction "A1_2") (pintype "input"))
      (node (ref "IC11") (pin "8") (pinfunction "VCC_8") (pintype "input"))
      (node (ref "IC7") (pin "8") (pinfunction "VCC_8") (pintype "input"))
      (node (ref "IC9") (pin "3") (pinfunction "/WP_3") (pintype "input"))
      (node (ref "IC9") (pin "7") (pinfunction "/HOLD_7") (pintype "input"))
      (node (ref "IC9") (pin "8") (pinfunction "VCC_8") (pintype "input"))
      (node (ref "Q2") (pin "3") (pinfunction "D_3") (pintype "passive"))
      (node (ref "Q2") (pin "P2") (pinfunction "D1_P2") (pintype "passive"))
      (node (ref "R18") (pin "1") (pinfunction "1_1") (pintype "passive"))
      (node (ref "R25") (pin "2") (pinfunction "2_2") (pintype "passive"))
      (node (ref "R26") (pin "1") (pinfunction "1_1") (pintype "passive"))
      (node (ref "R27") (pin "1") (pinfunction "1_1") (pintype "passive"))
    )
    (net (code "3") (name "+3.3V{slash}2") (class "Default")
      (node (ref "C41") (pin "1") (pinfunction "1_1") (pintype "passive"))
      (node (ref "C86") (pin "+") (pinfunction "+_+") (pintype "passive"))
      (node (ref "IC12") (pin "8") (pinfunction "VCC_8") (pintype "input"))
      (node (ref "Q1") (pin "3") (pinfunction "D_3") (pintype "passive"))
      (node (ref "Q1") (pin "P2") (pinfunction "D1_P2") (pintype "passive"))
      (node (ref "R30") (pin "2") (pinfunction "2_2") (pintype "passive"))
      (node (ref "R34") (pin "1") (pinfunction "1_1") (pintype "passive"))
      (node (ref "R72") (pin "1") (pinfunction "1_1") (pintype "passive"))
      (node (ref "R73") (pin "2") (pinfunction "2_2") (pintype "passive"))
    )
    (net (code "4") (name "A+") (class "Default")
      (node (ref "IC14") (pin "3") (pinfunction "3_3") (pintype "passive"))
      (node (ref "J3") (pin "4") (pinfunction "4_4") (pintype "passive"))
      (node (ref "J4") (pin "4") (pinfunction "4_4") (pintype "passive"))
      (node (ref "L8") (pin "2") (pinfunction "2_2") (pintype "passive"))
    )
    (net (code "5") (name "A++") (class "Default")
      (node (ref "IC12") (pin "6") (pinfunction "A_6") (pintype "bidirectional"))
      (node (ref "L8") (pin "1") (pinfunction "1_1") (pintype "passive"))
      (node (ref "R32") (pin "2") (pinfunction "2_2") (pintype "passive"))
      (node (ref "R34") (pin "2") (pinfunction "2_2") (pintype "passive"))
    )
    (net (code "6") (name "ACT-L-SENSE") (class "Default")
      (node (ref "IC1") (pin "92") (pinfunction "TRD3/CTED8/RA7_92") (pintype "bidirectional"))
      (node (ref "R1") (pin "7") (pinfunction "2_7") (pintype "passive"))
      (node (ref "R1") (pin "8") (pinfunction "2_8") (pintype "passive"))
    )
    (net (code "7") (name "ACT-L-SW") (class "Default")
      (node (ref "C44") (pin "1") (pinfunction "1_1") (pintype "passive"))
      (node (ref "J14") (pin "2") (pinfunction "2_2") (pintype "passive"))
      (node (ref "R1") (pin "1") (pinfunction "1_1") (pintype "passive"))
      (node (ref "R2") (pin "8") (pinfunction "2_8") (pintype "passive"))
    )
    (net (code "8") (name "ACT-R-SENSE") (class "Default")
      (node (ref "IC1") (pin "91") (pinfunction "TRCLK/RA6_91") (pintype "bidirectional"))
      (node (ref "R1") (pin "5") (pinfunction "2_5") (pintype "passive"))
      (node (ref "R1") (pin "6") (pinfunction "2_6") (pintype "passive"))
    )
    (net (code "9") (name "ACT-R-SW") (class "Default")
      (node (ref "C3") (pin "1") (pinfunction "1_1") (pintype "passive"))
      (node (ref "J15") (pin "2") (pinfunction "2_2") (pintype "passive"))
      (node (ref "R1") (pin "3") (pinfunction "1_3") (pintype "passive"))
      (node (ref "R2") (pin "7") (pinfunction "2_7") (pintype "passive"))
    )
    (net (code "10") (name "ACT_EN") (class "Default")
      (node (ref "IC1") (pin "77") (pinfunction "AN25/RPD2/RD2_77") (pintype "bidirectional"))
      (node (ref "R11") (pin "5") (pinfunction "2_5") (pintype "passive"))
      (node (ref "R11") (pin "6") (pinfunction "2_6") (pintype "passive"))
      (node (ref "R7") (pin "4") (pinfunction "1_4") (pintype "passive"))
    )
    (net (code "11") (name "ACT_L+") (class "Default")
      (node (ref "IC2") (pin "31") (pinfunction "OUT1A_31") (pintype "output"))
      (node (ref "J14") (pin "1") (pinfunction "1_1") (pintype "passive"))
    )
    (net (code "12") (name "ACT_L-") (class "Default")
      (node (ref "IC2") (pin "23") (pinfunction "OUT2A_23") (pintype "output"))
      (node (ref "J14") (pin "3") (pinfunction "3_3") (pintype "passive"))
    )
    (net (code "13") (name "ACT_L1") (class "Default")
      (node (ref "IC1") (pin "49") (pinfunction "RPF4/PMA9/RF4_49") (pintype "bidirectional"))
      (node (ref "IC2") (pin "27") (pinfunction "IN1_A_27") (pintype "input"))
      (node (ref "R10") (pin "5") (pinfunction "2_5") (pintype "passive"))
    )
    (net (code "14") (name "ACT_L2") (class "Default")
      (node (ref "IC2") (pin "28") (pinfunction "IN2_A_28") (pintype "input"))
      (node (ref "R10") (pin "6") (pinfunction "2_6") (pintype "passive"))
    )
    (net (code "15") (name "ACT_R+") (class "Default")
      (node (ref "IC2") (pin "9") (pinfunction "OUT1B_9") (pintype "output"))
      (node (ref "J15") (pin "1") (pinfunction "1_1") (pintype "passive"))
    )
    (net (code "16") (name "ACT_R-") (class "Default")
      (node (ref "IC2") (pin "19") (pinfunction "OUT2B_19") (pintype "output"))
      (node (ref "J15") (pin "3") (pinfunction "3_3") (pintype "passive"))
    )
    (net (code "17") (name "ACT_R1") (class "Default")
      (node (ref "IC1") (pin "50") (pinfunction "RPF5/PMA8/RF5_50") (pintype "bidirectional"))
      (node (ref "IC2") (pin "13") (pinfunction "IN1_B_13") (pintype "input"))
      (node (ref "R10") (pin "7") (pinfunction "2_7") (pintype "passive"))
    )
    (net (code "18") (name "ACT_R2") (class "Default")
      (node (ref "IC2") (pin "14") (pinfunction "IN2_B_14") (pintype "input"))
      (node (ref "R10") (pin "8") (pinfunction "2_8") (pintype "passive"))
    )
    (net (code "19") (name "B-") (class "Default")
      (node (ref "IC14") (pin "2") (pinfunction "2_2") (pintype "passive"))
      (node (ref "J3") (pin "5") (pinfunction "5_5") (pintype "passive"))
      (node (ref "J4") (pin "5") (pinfunction "5_5") (pintype "passive"))
      (node (ref "L7") (pin "2") (pinfunction "2_2") (pintype "passive"))
    )
    (net (code "20") (name "B--") (class "Default")
      (node (ref "IC12") (pin "7") (pinfunction "B_7") (pintype "bidirectional"))
      (node (ref "L7") (pin "1") (pinfunction "1_1") (pintype "passive"))
      (node (ref "R31") (pin "1") (pinfunction "1_1") (pintype "passive"))
      (node (ref "R32") (pin "1") (pinfunction "1_1") (pintype "passive"))
    )
    (net (code "21") (name "BT-RTS") (class "Default")
      (node (ref "CON2") (pin "7") (pinfunction "7_7") (pintype "bidirectional"))
      (node (ref "IC1") (pin "83") (pinfunction "PMD14/RD6_83") (pintype "bidirectional"))
      (node (ref "T44") (pin "P$1") (pinfunction "TP_P$1") (pintype "passive"))
    )
    (net (code "22") (name "BT-RX") (class "Default")
      (node (ref "CON2") (pin "3") (pinfunction "3_3") (pintype "bidirectional"))
      (node (ref "IC1") (pin "73") (pinfunction "SOSCI/RPC13/RC13_73") (pintype "bidirectional"))
      (node (ref "T40") (pin "P$1") (pinfunction "TP_P$1") (pintype "passive"))
    )
    (net (code "23") (name "BT-TX") (class "Default")
      (node (ref "CON2") (pin "4") (pinfunction "4_4") (pintype "bidirectional"))
      (node (ref "IC1") (pin "74") (pinfunction "SOSCO/RPC14/T1CK/RC14_74") (pintype "bidirectional"))
      (node (ref "T41") (pin "P$1") (pinfunction "TP_P$1") (pintype "passive"))
    )
    (net (code "24") (name "CON-LED") (class "Default")
      (node (ref "CON2") (pin "6") (pinfunction "6_6") (pintype "bidirectional"))
      (node (ref "IC1") (pin "78") (pinfunction "AN26/RPD3/RD3_78") (pintype "bidirectional"))
      (node (ref "T43") (pin "P$1") (pinfunction "TP_P$1") (pintype "passive"))
    )
    (net (code "25") (name "CURR-SENSE") (class "Default")
      (node (ref "C66") (pin "1") (pinfunction "1_1") (pintype "passive"))
      (node (ref "IC1") (pin "14") (pinfunction "AN19/C2INC/RPG9/PMA2/RG9_14") (pintype "bidirectional"))
      (node (ref "O8") (pin "P$1") (pinfunction "TP_P$1") (pintype "passive"))
      (node (ref "R102") (pin "2") (pinfunction "2_2") (pintype "passive"))
      (node (ref "T39") (pin "P$1") (pinfunction "TP_P$1") (pintype "passive"))
    )
    (net (code "26") (name "DGND") (class "Default")
      (node (ref "C10") (pin "2") (pinfunction "2_2") (pintype "passive"))
      (node (ref "C11") (pin "2") (pinfunction "2_2") (pintype "passive"))
      (node (ref "C13") (pin "2") (pinfunction "2_2") (pintype "passive"))
      (node (ref "C22") (pin "2") (pinfunction "2_2") (pintype "passive"))
      (node (ref "C23") (pin "2") (pinfunction "2_2") (pintype "passive"))
      (node (ref "C24") (pin "1") (pinfunction "1_1") (pintype "passive"))
      (node (ref "C27") (pin "2") (pinfunction "2_2") (pintype "passive"))
      (node (ref "C28") (pin "2") (pinfunction "2_2") (pintype "passive"))
      (node (ref "C29") (pin "2") (pinfunction "2_2") (pintype "passive"))
      (node (ref "C30") (pin "2") (pinfunction "2_2") (pintype "passive"))
      (node (ref "C31") (pin "-") (pinfunction "-_-") (pintype "passive"))
      (node (ref "C35") (pin "2") (pinfunction "2_2") (pintype "passive"))
      (node (ref "C36") (pin "2") (pinfunction "2_2") (pintype "passive"))
      (node (ref "C40") (pin "2") (pinfunction "2_2") (pintype "passive"))
      (node (ref "C41") (pin "2") (pinfunction "2_2") (pintype "passive"))
      (node (ref "C47") (pin "2") (pinfunction "2_2") (pintype "passive"))
      (node (ref "C48") (pin "2") (pinfunction "2_2") (pintype "passive"))
      (node (ref "C49") (pin "2") (pinfunction "2_2") (pintype "passive"))
      (node (ref "C50") (pin "2") (pinfunction "2_2") (pintype "passive"))
      (node (ref "C51") (pin "2") (pinfunction "2_2") (pintype "passive"))
      (node (ref "C52") (pin "2") (pinfunction "2_2") (pintype "passive"))
      (node (ref "C53") (pin "2") (pinfunction "2_2") (pintype "passive"))
      (node (ref "C54") (pin "-") (pinfunction "-_-") (pintype "passive"))
      (node (ref "C55") (pin "2") (pinfunction "2_2") (pintype "passive"))
      (node (ref "C56") (pin "-") (pinfunction "-_-") (pintype "passive"))
      (node (ref "C57") (pin "2") (pinfunction "2_2") (pintype "passive"))
      (node (ref "C58") (pin "2") (pinfunction "2_2") (pintype "passive"))
      (node (ref "C59") (pin "2") (pinfunction "2_2") (pintype "passive"))
      (node (ref "C60") (pin "2") (pinfunction "2_2") (pintype "passive"))
      (node (ref "C61") (pin "2") (pinfunction "2_2") (pintype "passive"))
      (node (ref "C62") (pin "2") (pinfunction "2_2") (pintype "passive"))
      (node (ref "C63") (pin "2") (pinfunction "2_2") (pintype "passive"))
      (node (ref "C64") (pin "2") (pinfunction "2_2") (pintype "passive"))
      (node (ref "C65") (pin "2") (pinfunction "2_2") (pintype "passive"))
      (node (ref "C66") (pin "2") (pinfunction "2_2") (pintype "passive"))
      (node (ref "C67") (pin "2") (pinfunction "2_2") (pintype "passive"))
      (node (ref "C81") (pin "-") (pinfunction "-_-") (pintype "passive"))
      (node (ref "C83") (pin "2") (pinfunction "2_2") (pintype "passive"))
      (node (ref "C84") (pin "2") (pinfunction "2_2") (pintype "passive"))
      (node (ref "C85") (pin "2") (pinfunction "2_2") (pintype "passive"))
      (node (ref "C86") (pin "-") (pinfunction "-_-") (pintype "passive"))
      (node (ref "C88") (pin "2") (pinfunction "2_2") (pintype "passive"))
      (node (ref "C9") (pin "2") (pinfunction "2_2") (pintype "passive"))
      (node (ref "CON2") (pin "1") (pinfunction "1_1") (pintype "bidirectional"))
      (node (ref "D2") (pin "-") (pinfunction "A_-") (pintype "passive"))
      (node (ref "D5") (pin "K") (pinfunction "K_K") (pintype "passive"))
      (node (ref "D7") (pin "A") (pinfunction "A_A") (pintype "passive"))
      (node (ref "H10") (pin "P1") (pinfunction "P$1_P1") (pintype "bidirectional"))
      (node (ref "H11") (pin "P1") (pinfunction "P$1_P1") (pintype "bidirectional"))
      (node (ref "H12") (pin "P1") (pinfunction "P$1_P1") (pintype "bidirectional"))
      (node (ref "H13") (pin "P1") (pinfunction "P$1_P1") (pintype "bidirectional"))
      (node (ref "H14") (pin "P1") (pinfunction "P$1_P1") (pintype "bidirectional"))
      (node (ref "H9") (pin "P1") (pinfunction "P$1_P1") (pintype "bidirectional"))
      (node (ref "IC1") (pin "15") (pinfunction "VSS2_15") (pintype "input"))
      (node (ref "IC1") (pin "31") (pinfunction "AVSS_31") (pintype "input"))
      (node (ref "IC1") (pin "36") (pinfunction "VSS3_36") (pintype "input"))
      (node (ref "IC1") (pin "45") (pinfunction "VSS4_45") (pintype "input"))
      (node (ref "IC1") (pin "65") (pinfunction "VSS5_65") (pintype "input"))
      (node (ref "IC1") (pin "75") (pinfunction "VSS1_75") (pintype "input"))
      (node (ref "IC10") (pin "1") (pinfunction "GND_1") (pintype "input"))
      (node (ref "IC10") (pin "2") (pinfunction "GND1_2") (pintype "input"))
      (node (ref "IC11") (pin "1") (pinfunction "A0_1") (pintype "input"))
      (node (ref "IC11") (pin "3") (pinfunction "A2_3") (pintype "input"))
      (node (ref "IC11") (pin "4") (pinfunction "GND_4") (pintype "input"))
      (node (ref "IC12") (pin "5") (pinfunction "GND_5") (pintype "input"))
      (node (ref "IC13") (pin "3") (pinfunction "GND_3") (pintype "bidirectional"))
      (node (ref "IC15") (pin "1") (pinfunction "1_1") (pintype "input"))
      (node (ref "IC16") (pin "4") (pinfunction "V-_4") (pintype "input"))
      (node (ref "IC3") (pin "10") (pinfunction "SYNC_10") (pintype "input"))
      (node (ref "IC3") (pin "EP") (pinfunction "GND_EP") (pintype "input"))
      (node (ref "IC6") (pin "2") (pinfunction "GND_2") (pintype "input"))
      (node (ref "IC7") (pin "1") (pinfunction "A0_1") (pintype "input"))
      (node (ref "IC7") (pin "2") (pinfunction "A1_2") (pintype "input"))
      (node (ref "IC7") (pin "3") (pinfunction "A2_3") (pintype "input"))
      (node (ref "IC7") (pin "4") (pinfunction "GND_4") (pintype "input"))
      (node (ref "IC7") (pin "7") (pinfunction "WP_7") (pintype "input"))
      (node (ref "IC9") (pin "4") (pinfunction "GND_4") (pintype "input"))
      (node (ref "J1") (pin "2") (pinfunction "2_2") (pintype "passive"))
      (node (ref "J12") (pin "4_GND") (pinfunction "GND_4_GND") (pintype "bidirectional"))
      (node (ref "J12") (pin "SH1") (pinfunction "GND_SH1_SH1") (pintype "bidirectional"))
      (node (ref "J12") (pin "SH2") (pinfunction "GND_SH2_SH2") (pintype "bidirectional"))
      (node (ref "J13") (pin "2") (pinfunction "2_2") (pintype "passive"))
      (node (ref "J17") (pin "3") (pinfunction "3_3") (pintype "passive"))
      (node (ref "J2") (pin "2") (pinfunction "2_2") (pintype "passive"))
      (node (ref "J5") (pin "2") (pinfunction "2_2") (pintype "passive"))
      (node (ref "J6") (pin "2") (pinfunction "2_2") (pintype "passive"))
      (node (ref "J7") (pin "2") (pinfunction "2_2") (pintype "passive"))
      (node (ref "L12") (pin "1") (pinfunction "1_1") (pintype "passive"))
      (node (ref "L2") (pin "2") (pinfunction "2_2") (pintype "passive"))
      (node (ref "R12") (pin "2") (pinfunction "2_2") (pintype "passive"))
      (node (ref "R14") (pin "1") (pinfunction "1_1") (pintype "passive"))
      (node (ref "R17") (pin "2") (pinfunction "2_2") (pintype "passive"))
      (node (ref "R19") (pin "2") (pinfunction "2_2") (pintype "passive"))
      (node (ref "R21") (pin "2") (pinfunction "2_2") (pintype "passive"))
      (node (ref "R31") (pin "2") (pinfunction "2_2") (pintype "passive"))
      (node (ref "R40") (pin "1") (pinfunction "1_1") (pintype "passive"))
      (node (ref "R41") (pin "2") (pinfunction "2_2") (pintype "passive"))
      (node (ref "R43") (pin "1") (pinfunction "1_1") (pintype "passive"))
      (node (ref "R44") (pin "2") (pinfunction "2_2") (pintype "passive"))
      (node (ref "R46") (pin "1") (pinfunction "1_1") (pintype "passive"))
      (node (ref "R48") (pin "1") (pinfunction "1_1") (pintype "passive"))
      (node (ref "R53") (pin "2") (pinfunction "1_2") (pintype "passive"))
      (node (ref "R53") (pin "4") (pinfunction "1_4") (pintype "passive"))
      (node (ref "R54") (pin "2") (pinfunction "1_2") (pintype "passive"))
      (node (ref "R54") (pin "4") (pinfunction "1_4") (pintype "passive"))
      (node (ref "R71") (pin "2") (pinfunction "2_2") (pintype "passive"))
      (node (ref "R96") (pin "2") (pinfunction "2_2") (pintype "passive"))
      (node (ref "R99") (pin "2") (pinfunction "2_2") (pintype "passive"))
    )
    (net (code "27") (name "DOOR_L") (class "Default")
      (node (ref "IC1") (pin "51") (pinfunction "RPF3/USBID/RF3_51") (pintype "bidirectional"))
      (node (ref "R50") (pin "2") (pinfunction "1_2") (pintype "passive"))
      (node (ref "R50") (pin "3") (pinfunction "1_3") (pintype "passive"))
    )
    (net (code "28") (name "DOOR_L_SW") (class "Default")
      (node (ref "C12") (pin "1") (pinfunction "1_1") (pintype "passive"))
      (node (ref "J1") (pin "1") (pinfunction "1_1") (pintype "passive"))
      (node (ref "J14") (pin "4") (pinfunction "4_4") (pintype "passive"))
      (node (ref "R50") (pin "7") (pinfunction "2_7") (pintype "passive"))
      (node (ref "R6") (pin "2") (pinfunction "2_2") (pintype "passive"))
    )
    (net (code "29") (name "DOOR_ON") (class "Default")
      (node (ref "IC1") (pin "89") (pinfunction "RPG1/PMD9/RG1_89") (pintype "bidirectional"))
      (node (ref "Q3") (pin "5") (pinfunction "Q1G_5") (pintype "input"))
      (node (ref "R9") (pin "7") (pinfunction "2_7") (pintype "passive"))
    )
    (net (code "30") (name "DOOR_R") (class "Default")
      (node (ref "IC1") (pin "23") (pinfunction "PGEC3/AN2/C2INB/RPB2/CTED13/RB2_23") (pintype "bidirectional"))
      (node (ref "R50") (pin "1") (pinfunction "1_1") (pintype "passive"))
      (node (ref "R50") (pin "4") (pinfunction "1_4") (pintype "passive"))
    )
    (net (code "31") (name "DOOR_R_SW") (class "Default")
      (node (ref "C4") (pin "1") (pinfunction "1_1") (pintype "passive"))
      (node (ref "J15") (pin "4") (pinfunction "4_4") (pintype "passive"))
      (node (ref "J7") (pin "1") (pinfunction "1_1") (pintype "passive"))
      (node (ref "R50") (pin "8") (pinfunction "2_8") (pintype "passive"))
      (node (ref "R8") (pin "2") (pinfunction "2_2") (pintype "passive"))
    )
    (net (code "32") (name "D_N") (class "Default")
      (node (ref "IC1") (pin "56") (pinfunction "D-/RG3_56") (pintype "bidirectional"))
      (node (ref "IC15") (pin "2") (pinfunction "2_2") (pintype "passive"))
      (node (ref "J12") (pin "2_D-") (pinfunction "D-_2_D-") (pintype "bidirectional"))
    )
    (net (code "33") (name "D_P") (class "Default")
      (node (ref "IC1") (pin "57") (pinfunction "D+/RG2_57") (pintype "bidirectional"))
      (node (ref "IC15") (pin "3") (pinfunction "3_3") (pintype "passive"))
      (node (ref "J12") (pin "3_D+") (pinfunction "D+_3_D+") (pintype "bidirectional"))
    )
    (net (code "34") (name "LAN-CTL") (class "Default")
      (node (ref "IC1") (pin "84") (pinfunction "PMD15/RD7_84") (pintype "bidirectional"))
      (node (ref "IC12") (pin "2") (pinfunction "/RE_2") (pintype "input"))
      (node (ref "IC12") (pin "3") (pinfunction "DE_3") (pintype "input"))
      (node (ref "O31") (pin "P$1") (pinfunction "TP_P$1") (pintype "passive"))
      (node (ref "R71") (pin "1") (pinfunction "1_1") (pintype "passive"))
      (node (ref "T15") (pin "P$1") (pinfunction "TP_P$1") (pintype "passive"))
    )
    (net (code "35") (name "LAN-RX") (class "Default")
      (node (ref "IC1") (pin "88") (pinfunction "RPF1/PMD10/RF1_88") (pintype "bidirectional"))
      (node (ref "IC12") (pin "1") (pinfunction "R_1") (pintype "output"))
      (node (ref "O29") (pin "P$1") (pinfunction "TP_P$1") (pintype "passive"))
      (node (ref "R72") (pin "2") (pinfunction "2_2") (pintype "passive"))
      (node (ref "T13") (pin "P$1") (pinfunction "TP_P$1") (pintype "passive"))
    )
    (net (code "36") (name "LAN-TX") (class "Default")
      (node (ref "IC1") (pin "87") (pinfunction "RPF0/PMD11/RF0_87") (pintype "bidirectional"))
      (node (ref "IC12") (pin "4") (pinfunction "D_4") (pintype "input"))
      (node (ref "O30") (pin "P$1") (pinfunction "TP_P$1") (pintype "passive"))
      (node (ref "R73") (pin "1") (pinfunction "1_1") (pintype "passive"))
      (node (ref "T14") (pin "P$1") (pinfunction "TP_P$1") (pintype "passive"))
    )
    (net (code "37") (name "LED-PIC") (class "Default")
      (node (ref "IC1") (pin "1") (pinfunction "RG15_1") (pintype "bidirectional"))
      (node (ref "O1") (pin "P$1") (pinfunction "TP_P$1") (pintype "passive"))
      (node (ref "R29") (pin "1") (pinfunction "1_1") (pintype "passive"))
      (node (ref "T36") (pin "P$1") (pinfunction "TP_P$1") (pintype "passive"))
      (node (ref "TP4") (pin "P$1") (pinfunction "TP_P$1") (pintype "passive"))
    )
    (net (code "38") (name "Net-(C24-Pad2)") (class "Default")
      (node (ref "C24") (pin "2") (pinfunction "2_2") (pintype "passive"))
      (node (ref "R77") (pin "2") (pinfunction "2_2") (pintype "passive"))
    )
    (net (code "39") (name "Net-(C39-Pad1)") (class "Default")
      (node (ref "C39") (pin "1") (pinfunction "1_1") (pintype "passive"))
      (node (ref "IC14") (pin "4") (pinfunction "4_4") (pintype "input"))
      (node (ref "R30") (pin "1") (pinfunction "1_1") (pintype "passive"))
    )
    (net (code "40") (name "Net-(C39-Pad2)") (class "Default")
      (node (ref "C39") (pin "2") (pinfunction "2_2") (pintype "passive"))
      (node (ref "D3") (pin "A") (pinfunction "A_A") (pintype "passive"))
      (node (ref "D4") (pin "A") (pinfunction "A_A") (pintype "passive"))
      (node (ref "IC14") (pin "1") (pinfunction "1_1") (pintype "input"))
      (node (ref "J3") (pin "2") (pinfunction "2_2") (pintype "passive"))
      (node (ref "J3") (pin "7") (pinfunction "7_7") (pintype "passive"))
      (node (ref "J3") (pin "8") (pinfunction "8_8") (pintype "passive"))
      (node (ref "J4") (pin "2") (pinfunction "2_2") (pintype "passive"))
      (node (ref "J4") (pin "7") (pinfunction "7_7") (pintype "passive"))
      (node (ref "J4") (pin "8") (pinfunction "8_8") (pintype "passive"))
      (node (ref "L12") (pin "2") (pinfunction "2_2") (pintype "passive"))
    )
    (net (code "41") (name "Net-(C40-Pad1)") (class "Default")
      (node (ref "C40") (pin "1") (pinfunction "1_1") (pintype "passive"))
      (node (ref "R90") (pin "1") (pinfunction "1_1") (pintype "passive"))
      (node (ref "R91") (pin "1") (pinfunction "1_1") (pintype "passive"))
    )
    (net (code "42") (name "Net-(D1-K)") (class "Default")
      (node (ref "C37") (pin "2") (pinfunction "2_2") (pintype "passive"))
      (node (ref "D1") (pin "2") (pinfunction "K_2") (pintype "passive"))
      (node (ref "IC2") (pin "17") (pinfunction "VBOOT_17") (pintype "input"))
    )
    (net (code "43") (name "Net-(D1-KA)") (class "Default")
      (node (ref "C2") (pin "1") (pinfunction "1_1") (pintype "passive"))
      (node (ref "D1") (pin "3") (pinfunction "KA_3") (pintype "passive"))
    )
    (net (code "44") (name "Net-(D2-C)") (class "Default")
      (node (ref "C26") (pin "1") (pinfunction "1_1") (pintype "passive"))
      (node (ref "C30") (pin "1") (pinfunction "1_1") (pintype "passive"))
      (node (ref "C31") (pin "+") (pinfunction "+_+") (pintype "passive"))
      (node (ref "D2") (pin "+") (pinfunction "C_+") (pintype "passive"))
      (node (ref "IC3") (pin "1") (pinfunction "BD_1") (pintype "input"))
      (node (ref "L9") (pin "2") (pinfunction "2_2") (pintype "passive"))
      (node (ref "R129") (pin "2") (pinfunction "2_2") (pintype "passive"))
      (node (ref "R20") (pin "1") (pinfunction "1_1") (pintype "passive"))
    )
    (net (code "45") (name "Net-(D5-PadA)") (class "Default")
      (node (ref "D5") (pin "A") (pinfunction "A_A") (pintype "passive"))
      (node (ref "R29") (pin "2") (pinfunction "2_2") (pintype "passive"))
    )
    (net (code "46") (name "Net-(D9-C)") (class "Default")
      (node (ref "D9") (pin "3") (pinfunction "C_3") (pintype "passive"))
      (node (ref "R2") (pin "1") (pinfunction "1_1") (pintype "passive"))
      (node (ref "R2") (pin "2") (pinfunction "1_2") (pintype "passive"))
      (node (ref "R7") (pin "6") (pinfunction "2_6") (pintype "passive"))
    )
    (net (code "47") (name "Net-(IC1-AVDD)") (class "Default")
      (node (ref "C55") (pin "1") (pinfunction "1_1") (pintype "passive"))
      (node (ref "C56") (pin "+") (pinfunction "+_+") (pintype "passive"))
      (node (ref "C88") (pin "1") (pinfunction "1_1") (pintype "passive"))
      (node (ref "IC1") (pin "30") (pinfunction "AVDD_30") (pintype "input"))
      (node (ref "R92") (pin "2") (pinfunction "2_2") (pintype "passive"))
    )
    (net (code "48") (name "Net-(IC1-CLKI{slash}RC12{slash}OSC1)") (class "Default")
      (node (ref "C60") (pin "1") (pinfunction "1_1") (pintype "passive"))
      (node (ref "IC1") (pin "63") (pinfunction "CLKI/RC12/OSC1_63") (pintype "bidirectional"))
      (node (ref "X1") (pin "3") (pinfunction "2_3") (pintype "passive"))
    )
    (net (code "49") (name "Net-(IC1-CLKO{slash}RC15{slash}OSC2)") (class "Default")
      (node (ref "C61") (pin "1") (pinfunction "1_1") (pintype "passive"))
      (node (ref "IC1") (pin "64") (pinfunction "CLKO/RC15/OSC2_64") (pintype "bidirectional"))
      (node (ref "X1") (pin "1") (pinfunction "1_1") (pintype "passive"))
    )
    (net (code "50") (name "Net-(IC1-VCAP)") (class "Default")
      (node (ref "C53") (pin "1") (pinfunction "1_1") (pintype "passive"))
      (node (ref "C54") (pin "+") (pinfunction "+_+") (pintype "passive"))
      (node (ref "IC1") (pin "85") (pinfunction "VCAP_85") (pintype "input"))
    )
    (net (code "51") (name "Net-(IC2-EN_A)") (class "Default")
      (node (ref "C5") (pin "1") (pinfunction "1_1") (pintype "passive"))
      (node (ref "IC2") (pin "25") (pinfunction "EN_A_25") (pintype "input"))
      (node (ref "R11") (pin "4") (pinfunction "1_4") (pintype "passive"))
    )
    (net (code "52") (name "Net-(IC2-EN_B)") (class "Default")
      (node (ref "C43") (pin "1") (pinfunction "1_1") (pintype "passive"))
      (node (ref "IC2") (pin "16") (pinfunction "EN_B_16") (pintype "input"))
      (node (ref "R11") (pin "3") (pinfunction "1_3") (pintype "passive"))
    )
    (net (code "53") (name "Net-(IC2-RCA)") (class "Default")
      (node (ref "C7") (pin "1") (pinfunction "1_1") (pintype "passive"))
      (node (ref "IC2") (pin "30") (pinfunction "RCA_30") (pintype "input"))
      (node (ref "R11") (pin "2") (pinfunction "1_2") (pintype "passive"))
    )
    (net (code "54") (name "Net-(IC2-RCB)") (class "Default")
      (node (ref "C6") (pin "1") (pinfunction "1_1") (pintype "passive"))
      (node (ref "IC2") (pin "11") (pinfunction "RCB_11") (pintype "input"))
      (node (ref "R11") (pin "1") (pinfunction "1_1") (pintype "passive"))
    )
    (net (code "55") (name "Net-(IC2-SENSE_A)") (class "Default")
      (node (ref "IC2") (pin "29") (pinfunction "SENSE_A_29") (pintype "input"))
      (node (ref "R5") (pin "2") (pinfunction "2_2") (pintype "passive"))
    )
    (net (code "56") (name "Net-(IC2-SENSE_B)") (class "Default")
      (node (ref "IC2") (pin "12") (pinfunction "SENSE_B_12") (pintype "input"))
      (node (ref "R4") (pin "2") (pinfunction "2_2") (pintype "passive"))
    )
    (net (code "57") (name "Net-(IC2-VCP)") (class "Default")
      (node (ref "C2") (pin "2") (pinfunction "2_2") (pintype "passive"))
      (node (ref "IC2") (pin "24") (pinfunction "VCP_24") (pintype "input"))
    )
    (net (code "58") (name "Net-(IC2-VREF_A)") (class "Default")
      (node (ref "IC2") (pin "15") (pinfunction "VREF_B_15") (pintype "input"))
      (node (ref "IC2") (pin "26") (pinfunction "VREF_A_26") (pintype "input"))
      (node (ref "R3") (pin "2") (pinfunction "2_2") (pintype "passive"))
      (node (ref "R7") (pin "5") (pinfunction "2_5") (pintype "passive"))
    )
    (net (code "59") (name "Net-(IC3-BOOST)") (class "Default")
      (node (ref "C25") (pin "2") (pinfunction "2_2") (pintype "passive"))
      (node (ref "IC3") (pin "2") (pinfunction "BOOST_2") (pintype "input"))
    )
    (net (code "60") (name "Net-(IC3-EN)") (class "Default")
      (node (ref "IC3") (pin "5") (pinfunction "EN_5") (pintype "input"))
      (node (ref "JP1") (pin "2") (pinfunction "2_2") (pintype "bidirectional"))
      (node (ref "R22") (pin "2") (pinfunction "2_2") (pintype "passive"))
    )
    (net (code "61") (name "Net-(IC3-FB)") (class "Default")
      (node (ref "C26") (pin "2") (pinfunction "2_2") (pintype "passive"))
      (node (ref "IC3") (pin "6") (pinfunction "FB_6") (pintype "input"))
      (node (ref "R19") (pin "1") (pinfunction "1_1") (pintype "passive"))
      (node (ref "R20") (pin "2") (pinfunction "2_2") (pintype "passive"))
    )
    (net (code "62") (name "Net-(IC3-RT)") (class "Default")
      (node (ref "IC3") (pin "8") (pinfunction "RT_8") (pintype "input"))
      (node (ref "R17") (pin "1") (pinfunction "1_1") (pintype "passive"))
    )
    (net (code "63") (name "Net-(IC3-SS)") (class "Default")
      (node (ref "IC3") (pin "7") (pinfunction "SS_7") (pintype "input"))
      (node (ref "R77") (pin "1") (pinfunction "1_1") (pintype "passive"))
    )
    (net (code "64") (name "Net-(IC3-SW)") (class "Default")
      (node (ref "C25") (pin "1") (pinfunction "1_1") (pintype "passive"))
      (node (ref "D7") (pin "K") (pinfunction "K_K") (pintype "passive"))
      (node (ref "IC3") (pin "3") (pinfunction "SW_3") (pintype "output"))
      (node (ref "L9") (pin "1") (pinfunction "1_1") (pintype "passive"))
    )
    (net (code "65") (name "Net-(IC6-HTH)") (class "Default")
      (node (ref "IC6") (pin "1") (pinfunction "HTH_1") (pintype "input"))
      (node (ref "R46") (pin "2") (pinfunction "2_2") (pintype "passive"))
      (node (ref "R47") (pin "1") (pinfunction "1_1") (pintype "passive"))
    )
    (net (code "66") (name "Net-(IC6-LTH)") (class "Default")
      (node (ref "IC6") (pin "3") (pinfunction "LTH_3") (pintype "input"))
      (node (ref "R33") (pin "1") (pinfunction "1_1") (pintype "passive"))
      (node (ref "R47") (pin "2") (pinfunction "2_2") (pintype "passive"))
    )
    (net (code "67") (name "Net-(IC6-VDD)") (class "Default")
      (node (ref "C35") (pin "1") (pinfunction "1_1") (pintype "passive"))
      (node (ref "IC6") (pin "5") (pinfunction "VDD_5") (pintype "input"))
      (node (ref "R28") (pin "1") (pinfunction "1_1") (pintype "passive"))
    )
    (net (code "68") (name "Net-(IC10-OUT)") (class "Default")
      (node (ref "IC10") (pin "3") (pinfunction "OUT_3") (pintype "output"))
      (node (ref "R102") (pin "1") (pinfunction "1_1") (pintype "passive"))
    )
    (net (code "69") (name "Net-(IC10-VIN+)") (class "Default")
      (node (ref "C29") (pin "1") (pinfunction "1_1") (pintype "passive"))
      (node (ref "F1") (pin "1") (pinfunction "1_1") (pintype "passive"))
      (node (ref "IC10") (pin "5") (pinfunction "VIN+_5") (pintype "input"))
      (node (ref "R39") (pin "2") (pinfunction "2_2") (pintype "passive"))
    )
    (net (code "70") (name "Net-(IC11-WP)") (class "Default")
      (node (ref "IC11") (pin "7") (pinfunction "WP_7") (pintype "input"))
      (node (ref "R18") (pin "2") (pinfunction "2_2") (pintype "passive"))
      (node (ref "TP1") (pin "P$1") (pinfunction "TP_P$1") (pintype "passive"))
    )
    (net (code "71") (name "Net-(IC13-VIN)") (class "Default")
      (node (ref "C58") (pin "1") (pinfunction "1_1") (pintype "passive"))
      (node (ref "C59") (pin "1") (pinfunction "1_1") (pintype "passive"))
      (node (ref "IC13") (pin "1") (pinfunction "VIN_1") (pintype "bidirectional"))
      (node (ref "R93") (pin "2") (pinfunction "2_2") (pintype "passive"))
    )
    (net (code "72") (name "Net-(IC16A-+IN)") (class "Default")
      (node (ref "C62") (pin "1") (pinfunction "1_1") (pintype "passive"))
      (node (ref "IC16") (pin "3") (pinfunction "+IN_3") (pintype "input"))
      (node (ref "R95") (pin "2") (pinfunction "2_2") (pintype "passive"))
      (node (ref "R96") (pin "1") (pinfunction "1_1") (pintype "passive"))
    )
    (net (code "73") (name "Net-(IC16A--IN)") (class "Default")
      (node (ref "IC16") (pin "1") (pinfunction "OUT_1") (pintype "output"))
      (node (ref "IC16") (pin "2") (pinfunction "-IN_2") (pintype "input"))
      (node (ref "R101") (pin "2") (pinfunction "2_2") (pintype "passive"))
    )
    (net (code "74") (name "Net-(IC16B-+IN)") (class "Default")
      (node (ref "C63") (pin "1") (pinfunction "1_1") (pintype "passive"))
      (node (ref "IC16") (pin "5") (pinfunction "+IN_5") (pintype "input"))
      (node (ref "R98") (pin "2") (pinfunction "2_2") (pintype "passive"))
      (node (ref "R99") (pin "1") (pinfunction "1_1") (pintype "passive"))
    )
    (net (code "75") (name "Net-(IC16B--IN)") (class "Default")
      (node (ref "IC16") (pin "6") (pinfunction "-IN_6") (pintype "input"))
      (node (ref "IC16") (pin "7") (pinfunction "OUT_7") (pintype "output"))
      (node (ref "R100") (pin "2") (pinfunction "2_2") (pintype "passive"))
    )
    (net (code "76") (name "Net-(IC16C-V+)") (class "Default")
      (node (ref "C67") (pin "1") (pinfunction "1_1") (pintype "passive"))
      (node (ref "IC16") (pin "8") (pinfunction "V+_8") (pintype "input"))
      (node (ref "R103") (pin "1") (pinfunction "1_1") (pintype "passive"))
    )
    (net (code "77") (name "Net-(J12-+5V)") (class "Default")
      (node (ref "C85") (pin "1") (pinfunction "1_1") (pintype "passive"))
      (node (ref "D6") (pin "A") (pinfunction "A_A") (pintype "passive"))
      (node (ref "IC15") (pin "4") (pinfunction "4_4") (pintype "input"))
      (node (ref "J12") (pin "1_+5V") (pinfunction "+5V_1_+5V") (pintype "bidirectional"))
      (node (ref "R128") (pin "1") (pinfunction "1_1") (pintype "passive"))
    )
    (net (code "78") (name "Net-(JP1-Pad1)") (class "Default")
      (node (ref "JP1") (pin "1") (pinfunction "1_1") (pintype "bidirectional"))
      (node (ref "R21") (pin "1") (pinfunction "1_1") (pintype "passive"))
    )
    (net (code "79") (name "Net-(L13-Pad2)") (class "Default")
      (node (ref "L13") (pin "2") (pinfunction "2_2") (pintype "passive"))
      (node (ref "R92") (pin "1") (pinfunction "1_1") (pintype "passive"))
    )
    (net (code "80") (name "Net-(Q1B-G)") (class "Default")
      (node (ref "C70") (pin "2") (pinfunction "2_2") (pintype "passive"))
      (node (ref "Q1") (pin "5") (pinfunction "G_5") (pintype "passive"))
      (node (ref "R75") (pin "1") (pinfunction "1_1") (pintype "passive"))
      (node (ref "R82") (pin "2") (pinfunction "2_2") (pintype "passive"))
    )
    (net (code "81") (name "Net-(Q1B-S)") (class "Default")
      (node (ref "Q1") (pin "4") (pinfunction "S_4") (pintype "passive"))
      (node (ref "R106") (pin "1") (pinfunction "1_1") (pintype "passive"))
    )
    (net (code "82") (name "Net-(Q2B-G)") (class "Default")
      (node (ref "C69") (pin "2") (pinfunction "2_2") (pintype "passive"))
      (node (ref "Q2") (pin "5") (pinfunction "G_5") (pintype "passive"))
      (node (ref "R24") (pin "1") (pinfunction "1_1") (pintype "passive"))
      (node (ref "R65") (pin "2") (pinfunction "2_2") (pintype "passive"))
    )
    (net (code "83") (name "Net-(Q2B-S)") (class "Default")
      (node (ref "Q2") (pin "4") (pinfunction "S_4") (pintype "passive"))
      (node (ref "R105") (pin "1") (pinfunction "1_1") (pintype "passive"))
    )
    (net (code "84") (name "Net-(Q3-Q2D1)") (class "Default")
      (node (ref "Q3") (pin "2") (pinfunction "Q2D1_2") (pintype "bidirectional"))
      (node (ref "Q3") (pin "3") (pinfunction "Q2D2_3") (pintype "bidirectional"))
      (node (ref "R15") (pin "1") (pinfunction "1_1") (pintype "passive"))
      (node (ref "R16") (pin "1") (pinfunction "1_1") (pintype "passive"))
      (node (ref "R51") (pin "1") (pinfunction "1_1") (pintype "passive"))
      (node (ref "R52") (pin "1") (pinfunction "1_1") (pintype "passive"))
      (node (ref "R6") (pin "1") (pinfunction "1_1") (pintype "passive"))
      (node (ref "R8") (pin "1") (pinfunction "1_1") (pintype "passive"))
    )
    (net (code "85") (name "Net-(Q3-Q2G)") (class "Default")
      (node (ref "Q3") (pin "6") (pinfunction "Q2G_6") (pintype "input"))
      (node (ref "R9") (pin "3") (pinfunction "1_3") (pintype "passive"))
    )
    (net (code "86") (name "Net-(Q4A-D)") (class "Default")
      (node (ref "C33") (pin "2") (pinfunction "2_2") (pintype "passive"))
      (node (ref "Q4") (pin "6") (pinfunction "D_6") (pintype "passive"))
      (node (ref "Q5") (pin "1") (pinfunction "G_1") (pintype "passive"))
      (node (ref "R42") (pin "2") (pinfunction "2_2") (pintype "passive"))
    )
    (net (code "87") (name "Net-(Q4A-S)") (class "Default")
      (node (ref "Q4") (pin "1") (pinfunction "S_1") (pintype "passive"))
      (node (ref "R40") (pin "2") (pinfunction "2_2") (pintype "passive"))
    )
    (net (code "88") (name "Net-(Q4B-D)") (class "Default")
      (node (ref "C34") (pin "2") (pinfunction "2_2") (pintype "passive"))
      (node (ref "Q4") (pin "3") (pinfunction "D_3") (pintype "passive"))
      (node (ref "Q5") (pin "3") (pinfunction "G_3") (pintype "passive"))
      (node (ref "R45") (pin "2") (pinfunction "2_2") (pintype "passive"))
    )
    (net (code "89") (name "Net-(Q4B-S)") (class "Default")
      (node (ref "Q4") (pin "4") (pinfunction "S_4") (pintype "passive"))
      (node (ref "R43") (pin "2") (pinfunction "2_2") (pintype "passive"))
    )
    (net (code "90") (name "Net-(Q5A-D)") (class "Default")
      (node (ref "F1") (pin "2") (pinfunction "2_2") (pintype "passive"))
      (node (ref "Q5") (pin "6") (pinfunction "D_6") (pintype "passive"))
      (node (ref "R35") (pin "1") (pinfunction "1_1") (pintype "passive"))
      (node (ref "R37") (pin "1") (pinfunction "1_1") (pintype "passive"))
      (node (ref "R97") (pin "1") (pinfunction "1_1") (pintype "passive"))
    )
    (net (code "91") (name "Net-(Q6A-D)") (class "Default")
      (node (ref "C8") (pin "2") (pinfunction "2_2") (pintype "passive"))
      (node (ref "Q6") (pin "6") (pinfunction "D_6") (pintype "passive"))
      (node (ref "Q7") (pin "1") (pinfunction "G_1") (pintype "passive"))
      (node (ref "R13") (pin "2") (pinfunction "2_2") (pintype "passive"))
    )
    (net (code "92") (name "Net-(Q6A-S)") (class "Default")
      (node (ref "Q6") (pin "1") (pinfunction "S_1") (pintype "passive"))
      (node (ref "R14") (pin "2") (pinfunction "2_2") (pintype "passive"))
    )
    (net (code "93") (name "Net-(R23-Pad1)") (class "Default")
      (node (ref "R23") (pin "1") (pinfunction "1_1") (pintype "passive"))
      (node (ref "R49") (pin "2") (pinfunction "2_2") (pintype "passive"))
    )
    (net (code "94") (name "Net-(R35-Pad2)") (class "Default")
      (node (ref "R35") (pin "2") (pinfunction "2_2") (pintype "passive"))
      (node (ref "R36") (pin "1") (pinfunction "1_1") (pintype "passive"))
      (node (ref "R37") (pin "2") (pinfunction "2_2") (pintype "passive"))
      (node (ref "R38") (pin "1") (pinfunction "1_1") (pintype "passive"))
    )
    (net (code "95") (name "Net-(R53A-2)") (class "Default")
      (node (ref "C9") (pin "1") (pinfunction "1_1") (pintype "passive"))
      (node (ref "J13") (pin "1") (pinfunction "1_1") (pintype "passive"))
      (node (ref "R15") (pin "2") (pinfunction "2_2") (pintype "passive"))
      (node (ref "R53") (pin "8") (pinfunction "2_8") (pintype "passive"))
    )
    (net (code "96") (name "Net-(R53C-2)") (class "Default")
      (node (ref "C10") (pin "1") (pinfunction "1_1") (pintype "passive"))
      (node (ref "J2") (pin "1") (pinfunction "1_1") (pintype "passive"))
      (node (ref "R16") (pin "2") (pinfunction "2_2") (pintype "passive"))
      (node (ref "R53") (pin "6") (pinfunction "2_6") (pintype "passive"))
    )
    (net (code "97") (name "Net-(R54A-2)") (class "Default")
      (node (ref "C11") (pin "1") (pinfunction "1_1") (pintype "passive"))
      (node (ref "J5") (pin "1") (pinfunction "1_1") (pintype "passive"))
      (node (ref "R51") (pin "2") (pinfunction "2_2") (pintype "passive"))
      (node (ref "R54") (pin "8") (pinfunction "2_8") (pintype "passive"))
    )
    (net (code "98") (name "Net-(R54C-2)") (class "Default")
      (node (ref "C13") (pin "1") (pinfunction "1_1") (pintype "passive"))
      (node (ref "J6") (pin "1") (pinfunction "1_1") (pintype "passive"))
      (node (ref "R52") (pin "2") (pinfunction "2_2") (pintype "passive"))
      (node (ref "R54") (pin "6") (pinfunction "2_6") (pintype "passive"))
    )
    (net (code "99") (name "Net-(R94-Pad2)") (class "Default")
      (node (ref "R94") (pin "2") (pinfunction "2_2") (pintype "passive"))
      (node (ref "R95") (pin "1") (pinfunction "1_1") (pintype "passive"))
    )
    (net (code "100") (name "Net-(R97-Pad2)") (class "Default")
      (node (ref "R97") (pin "2") (pinfunction "2_2") (pintype "passive"))
      (node (ref "R98") (pin "1") (pinfunction "1_1") (pintype "passive"))
    )
    (net (code "101") (name "PAL1") (class "Default")
      (node (ref "IC1") (pin "9") (pinfunction "RPC4/CTED7/RC4_9") (pintype "bidirectional"))
      (node (ref "O5") (pin "P$1") (pinfunction "TP_P$1") (pintype "passive"))
      (node (ref "R53") (pin "1") (pinfunction "1_1") (pintype "passive"))
      (node (ref "R53") (pin "7") (pinfunction "2_7") (pintype "passive"))
    )
    (net (code "102") (name "PAL2") (class "Default")
      (node (ref "IC1") (pin "18") (pinfunction "RPE8/RE8_18") (pintype "bidirectional"))
      (node (ref "R53") (pin "3") (pinfunction "1_3") (pintype "passive"))
      (node (ref "R53") (pin "5") (pinfunction "2_5") (pintype "passive"))
    )
    (net (code "103") (name "PAL3") (class "Default")
      (node (ref "IC1") (pin "19") (pinfunction "RPE9/RE9_19") (pintype "bidirectional"))
      (node (ref "R54") (pin "1") (pinfunction "1_1") (pintype "passive"))
      (node (ref "R54") (pin "7") (pinfunction "2_7") (pintype "passive"))
    )
    (net (code "104") (name "PAL4") (class "Default")
      (node (ref "IC1") (pin "42") (pinfunction "AN13/RB13_42") (pintype "bidirectional"))
      (node (ref "R54") (pin "3") (pinfunction "1_3") (pintype "passive"))
      (node (ref "R54") (pin "5") (pinfunction "2_5") (pintype "passive"))
    )
    (net (code "105") (name "PGC") (class "Default")
      (node (ref "IC1") (pin "24") (pinfunction "PGEC1/AN1/RPB1/CTED12/RB1_24") (pintype "bidirectional"))
      (node (ref "J17") (pin "5") (pinfunction "5_5") (pintype "passive"))
    )
    (net (code "106") (name "PGD") (class "Default")
      (node (ref "IC1") (pin "25") (pinfunction "PGED1/AN0/RPB0/RB0_25") (pintype "bidirectional"))
      (node (ref "J17") (pin "4") (pinfunction "4_4") (pintype "passive"))
      (node (ref "R130") (pin "2") (pinfunction "2_2") (pintype "passive"))
    )
    (net (code "107") (name "PGND") (class "Default")
      (node (ref "C1") (pin "2") (pinfunction "2_2") (pintype "passive"))
      (node (ref "C12") (pin "2") (pinfunction "2_2") (pintype "passive"))
      (node (ref "C3") (pin "2") (pinfunction "2_2") (pintype "passive"))
      (node (ref "C38") (pin "2") (pinfunction "2_2") (pintype "passive"))
      (node (ref "C4") (pin "2") (pinfunction "2_2") (pintype "passive"))
      (node (ref "C43") (pin "2") (pinfunction "2_2") (pintype "passive"))
      (node (ref "C44") (pin "2") (pinfunction "2_2") (pintype "passive"))
      (node (ref "C5") (pin "2") (pinfunction "2_2") (pintype "passive"))
      (node (ref "C6") (pin "2") (pinfunction "2_2") (pintype "passive"))
      (node (ref "C7") (pin "2") (pinfunction "2_2") (pintype "passive"))
      (node (ref "D8") (pin "A") (pinfunction "A_A") (pintype "passive"))
      (node (ref "D9") (pin "1") (pinfunction "A_1") (pintype "passive"))
      (node (ref "IC2") (pin "1") (pinfunction "GND1_1") (pintype "input"))
      (node (ref "IC2") (pin "2") (pinfunction "GND2_2") (pintype "input"))
      (node (ref "IC2") (pin "21") (pinfunction "GND21_21") (pintype "input"))
      (node (ref "IC2") (pin "3") (pinfunction "GND3_3") (pintype "input"))
      (node (ref "IC2") (pin "4") (pinfunction "GND4_4") (pintype "input"))
      (node (ref "IC2") (pin "5") (pinfunction "GND5_5") (pintype "input"))
      (node (ref "IC2") (pin "6") (pinfunction "GND6_6") (pintype "input"))
      (node (ref "IC2") (pin "7") (pinfunction "GND7_7") (pintype "input"))
      (node (ref "IC2") (pin "8") (pinfunction "GND8_8") (pintype "input"))
      (node (ref "IC2") (pin "G") (pinfunction "GNEXP_G") (pintype "input"))
      (node (ref "J14") (pin "5") (pinfunction "5_5") (pintype "passive"))
      (node (ref "J15") (pin "5") (pinfunction "5_5") (pintype "passive"))
      (node (ref "L2") (pin "1") (pinfunction "1_1") (pintype "passive"))
      (node (ref "Q3") (pin "1") (pinfunction "Q1S_1") (pintype "bidirectional"))
      (node (ref "R1") (pin "2") (pinfunction "1_2") (pintype "passive"))
      (node (ref "R1") (pin "4") (pinfunction "1_4") (pintype "passive"))
      (node (ref "R10") (pin "1") (pinfunction "1_1") (pintype "passive"))
      (node (ref "R10") (pin "2") (pinfunction "1_2") (pintype "passive"))
      (node (ref "R10") (pin "3") (pinfunction "1_3") (pintype "passive"))
      (node (ref "R10") (pin "4") (pinfunction "1_4") (pintype "passive"))
      (node (ref "R11") (pin "7") (pinfunction "2_7") (pintype "passive"))
      (node (ref "R11") (pin "8") (pinfunction "2_8") (pintype "passive"))
      (node (ref "R3") (pin "1") (pinfunction "1_1") (pintype "passive"))
      (node (ref "R4") (pin "1") (pinfunction "1_1") (pintype "passive"))
      (node (ref "R5") (pin "1") (pinfunction "1_1") (pintype "passive"))
      (node (ref "R50") (pin "5") (pinfunction "2_5") (pintype "passive"))
      (node (ref "R50") (pin "6") (pinfunction "2_6") (pintype "passive"))
      (node (ref "R9") (pin "2") (pinfunction "1_2") (pintype "passive"))
    )
    (net (code "108") (name "POWER-GOOD") (class "Default")
      (node (ref "IC6") (pin "4") (pinfunction "OUT_4") (pintype "output"))
      (node (ref "R130") (pin "1") (pinfunction "1_1") (pintype "passive"))
      (node (ref "T45") (pin "P$1") (pinfunction "TP_P$1") (pintype "passive"))
      (node (ref "TP2") (pin "P$1") (pinfunction "TP_P$1") (pintype "passive"))
    )
    (net (code "109") (name "REF-EN") (class "Default")
      (node (ref "IC1") (pin "28") (pinfunction "VREF-/CVREF-/PMA7/RA9_28") (pintype "bidirectional"))
      (node (ref "R93") (pin "1") (pinfunction "1_1") (pintype "passive"))
    )
    (net (code "110") (name "REF2,5V") (class "Default")
      (node (ref "C57") (pin "1") (pinfunction "1_1") (pintype "passive"))
      (node (ref "IC1") (pin "29") (pinfunction "VREF+/CVREF+/PMA6/RA10_29") (pintype "bidirectional"))
      (node (ref "IC13") (pin "2") (pinfunction "VOUT_2") (pintype "bidirectional"))
    )
    (net (code "111") (name "SCL1-EEPROM") (class "Default")
      (node (ref "IC1") (pin "66") (pinfunction "SCL1/RPA14/RA14_66") (pintype "bidirectional"))
      (node (ref "IC11") (pin "6") (pinfunction "SCL_6") (pintype "input"))
      (node (ref "IC7") (pin "6") (pinfunction "SCL_6") (pintype "input"))
      (node (ref "R26") (pin "2") (pinfunction "2_2") (pintype "passive"))
    )
    (net (code "112") (name "SCLK2-SPI") (class "Default")
      (node (ref "IC1") (pin "10") (pinfunction "AN16/C1IND/RPG6/SCK2/PMA5/RG6_10") (pintype "bidirectional"))
      (node (ref "IC9") (pin "6") (pinfunction "C_6") (pintype "input"))
    )
    (net (code "113") (name "SDA1-EEPROM") (class "Default")
      (node (ref "IC1") (pin "67") (pinfunction "SDA1/RPA15/RA15_67") (pintype "bidirectional"))
      (node (ref "IC11") (pin "5") (pinfunction "SDA_5") (pintype "bidirectional"))
      (node (ref "IC7") (pin "5") (pinfunction "SDA_5") (pintype "bidirectional"))
      (node (ref "R27") (pin "2") (pinfunction "2_2") (pintype "passive"))
    )
    (net (code "114") (name "SDI2-MISO") (class "Default")
      (node (ref "IC1") (pin "22") (pinfunction "PGED3/AN3/C2INA/RPB3/RB3_22") (pintype "bidirectional"))
      (node (ref "IC9") (pin "2") (pinfunction "Q_2") (pintype "bidirectional"))
      (node (ref "O13") (pin "P$1") (pinfunction "TP_P$1") (pintype "passive"))
    )
    (net (code "115") (name "SDO2-MOSI") (class "Default")
      (node (ref "IC1") (pin "20") (pinfunction "AN5/C1INA/RPB5/RB5_20") (pintype "bidirectional"))
      (node (ref "IC9") (pin "5") (pinfunction "D_5") (pintype "input"))
      (node (ref "O12") (pin "P$1") (pinfunction "TP_P$1") (pintype "passive"))
    )
    (net (code "116") (name "VACT") (class "Default")
      (node (ref "C1") (pin "1") (pinfunction "1_1") (pintype "passive"))
      (node (ref "C37") (pin "1") (pinfunction "1_1") (pintype "passive"))
      (node (ref "C38") (pin "1") (pinfunction "1_1") (pintype "passive"))
      (node (ref "D1") (pin "1") (pinfunction "A_1") (pintype "passive"))
      (node (ref "D8") (pin "C") (pinfunction "C_C") (pintype "passive"))
      (node (ref "IC2") (pin "20") (pinfunction "VS_B_20") (pintype "input"))
      (node (ref "IC2") (pin "22") (pinfunction "VS_A_22") (pintype "input"))
      (node (ref "Q7") (pin "6") (pinfunction "D_6") (pintype "passive"))
      (node (ref "R7") (pin "3") (pinfunction "1_3") (pintype "passive"))
    )
    (net (code "117") (name "VACT-ON") (class "Default")
      (node (ref "Q6") (pin "2") (pinfunction "G_2") (pintype "passive"))
      (node (ref "R12") (pin "1") (pinfunction "1_1") (pintype "passive"))
      (node (ref "T1") (pin "P$1") (pinfunction "TP_P$1") (pintype "passive"))
    )
    (net (code "118") (name "VBAT") (class "Default")
      (node (ref "C22") (pin "1") (pinfunction "1_1") (pintype "passive"))
      (node (ref "C23") (pin "1") (pinfunction "1_1") (pintype "passive"))
      (node (ref "C8") (pin "1") (pinfunction "1_1") (pintype "passive"))
      (node (ref "C83") (pin "1") (pinfunction "1_1") (pintype "passive"))
      (node (ref "C84") (pin "1") (pinfunction "1_1") (pintype "passive"))
      (node (ref "IC10") (pin "4") (pinfunction "VIN-_4") (pintype "input"))
      (node (ref "IC3") (pin "4") (pinfunction "VIN_4") (pintype "input"))
      (node (ref "JP1") (pin "3") (pinfunction "3_3") (pintype "bidirectional"))
      (node (ref "Q3") (pin "4") (pinfunction "Q2S_4") (pintype "bidirectional"))
      (node (ref "Q7") (pin "5") (pinfunction "S_5") (pintype "passive"))
      (node (ref "R13") (pin "1") (pinfunction "1_1") (pintype "passive"))
      (node (ref "R22") (pin "1") (pinfunction "1_1") (pintype "passive"))
      (node (ref "R33") (pin "2") (pinfunction "2_2") (pintype "passive"))
      (node (ref "R39") (pin "1") (pinfunction "1_1") (pintype "passive"))
      (node (ref "R9") (pin "6") (pinfunction "2_6") (pintype "passive"))
    )
    (net (code "119") (name "VBAT-LAN") (class "Default")
      (node (ref "D3") (pin "C") (pinfunction "C_C") (pintype "passive"))
      (node (ref "J3") (pin "1") (pinfunction "1_1") (pintype "passive"))
      (node (ref "J3") (pin "3") (pinfunction "3_3") (pintype "passive"))
      (node (ref "J4") (pin "1") (pinfunction "1_1") (pintype "passive"))
      (node (ref "J4") (pin "3") (pinfunction "3_3") (pintype "passive"))
      (node (ref "L11") (pin "2") (pinfunction "2_2") (pintype "passive"))
    )
    (net (code "120") (name "VBAT-LAN-F") (class "Default")
      (node (ref "C33") (pin "1") (pinfunction "1_1") (pintype "passive"))
      (node (ref "C34") (pin "1") (pinfunction "1_1") (pintype "passive"))
      (node (ref "D6") (pin "K") (pinfunction "K_K") (pintype "passive"))
      (node (ref "L11") (pin "1") (pinfunction "1_1") (pintype "passive"))
      (node (ref "Q5") (pin "2") (pinfunction "S_2") (pintype "passive"))
      (node (ref "Q5") (pin "5") (pinfunction "S_5") (pintype "passive"))
      (node (ref "R132") (pin "1") (pinfunction "1_1") (pintype "passive"))
      (node (ref "R36") (pin "2") (pinfunction "2_2") (pintype "passive"))
      (node (ref "R38") (pin "2") (pinfunction "2_2") (pintype "passive"))
      (node (ref "R42") (pin "1") (pinfunction "1_1") (pintype "passive"))
      (node (ref "R45") (pin "1") (pinfunction "1_1") (pintype "passive"))
      (node (ref "R94") (pin "1") (pinfunction "1_1") (pintype "passive"))
    )
    (net (code "121") (name "VBAT-ON") (class "Default")
      (node (ref "IC1") (pin "52") (pinfunction "RPF2/RF2_52") (pintype "bidirectional"))
      (node (ref "O42") (pin "P$1") (pinfunction "TP_P$1") (pintype "passive"))
      (node (ref "Q4") (pin "2") (pinfunction "G_2") (pintype "passive"))
      (node (ref "R132") (pin "2") (pinfunction "2_2") (pintype "passive"))
      (node (ref "R41") (pin "1") (pinfunction "1_1") (pintype "passive"))
      (node (ref "T5") (pin "P$1") (pinfunction "TP_P$1") (pintype "passive"))
    )
    (net (code "122") (name "VBAT-SENSE") (class "Default")
      (node (ref "C64") (pin "1") (pinfunction "1_1") (pintype "passive"))
      (node (ref "IC1") (pin "26") (pinfunction "PGEC2/AN6/RPB6/RB6_26") (pintype "bidirectional"))
      (node (ref "O15") (pin "P$1") (pinfunction "TP_P$1") (pintype "passive"))
      (node (ref "R100") (pin "1") (pinfunction "1_1") (pintype "passive"))
      (node (ref "T37") (pin "P$1") (pinfunction "TP_P$1") (pintype "passive"))
    )
    (net (code "123") (name "VBATLAN-SENSE") (class "Default")
      (node (ref "C36") (pin "1") (pinfunction "1_1") (pintype "passive"))
      (node (ref "IC1") (pin "27") (pinfunction "PGED2/AN7/RPB7/CTED3/RB7_27") (pintype "bidirectional"))
      (node (ref "O16") (pin "P$1") (pinfunction "TP_P$1") (pintype "passive"))
      (node (ref "R101") (pin "1") (pinfunction "1_1") (pintype "passive"))
      (node (ref "T38") (pin "P$1") (pinfunction "TP_P$1") (pintype "passive"))
    )
    (net (code "124") (name "VBUS") (class "Default")
      (node (ref "IC1") (pin "54") (pinfunction "VBUS_54") (pintype "input"))
      (node (ref "R128") (pin "2") (pinfunction "2_2") (pintype "passive"))
    )
    (net (code "125") (name "VPS-ON") (class "Default")
      (node (ref "IC1") (pin "53") (pinfunction "RPF8/RF8_53") (pintype "bidirectional"))
      (node (ref "O41") (pin "P$1") (pinfunction "TP_P$1") (pintype "passive"))
      (node (ref "Q4") (pin "5") (pinfunction "G_5") (pintype "passive"))
      (node (ref "R44") (pin "1") (pinfunction "1_1") (pintype "passive"))
      (node (ref "T7") (pin "P$1") (pinfunction "TP_P$1") (pintype "passive"))
    )
    (net (code "126") (name "VPS-PWR") (class "Default")
      (node (ref "D4") (pin "C") (pinfunction "C_C") (pintype "passive"))
      (node (ref "J3") (pin "6") (pinfunction "6_6") (pintype "passive"))
      (node (ref "J4") (pin "6") (pinfunction "6_6") (pintype "passive"))
      (node (ref "L10") (pin "2") (pinfunction "2_2") (pintype "passive"))
    )
    (net (code "127") (name "VPS-PWR-F") (class "Default")
      (node (ref "L10") (pin "1") (pinfunction "1_1") (pintype "passive"))
      (node (ref "Q5") (pin "4") (pinfunction "D_4") (pintype "passive"))
      (node (ref "R23") (pin "2") (pinfunction "2_2") (pintype "passive"))
    )
    (net (code "128") (name "VPS-SENSE") (class "Default")
      (node (ref "C65") (pin "1") (pinfunction "1_1") (pintype "passive"))
      (node (ref "IC1") (pin "12") (pinfunction "AN18/C2IND/RPG8/PMA3/RG8_12") (pintype "bidirectional"))
      (node (ref "O7") (pin "P$1") (pinfunction "TP_P$1") (pintype "passive"))
      (node (ref "R48") (pin "2") (pinfunction "2_2") (pintype "passive"))
      (node (ref "R49") (pin "1") (pinfunction "1_1") (pintype "passive"))
      (node (ref "T3") (pin "P$1") (pinfunction "TP_P$1") (pintype "passive"))
    )
    (net (code "129") (name "WAKE-SW") (class "Default")
      (node (ref "CON2") (pin "5") (pinfunction "5_5") (pintype "bidirectional"))
      (node (ref "IC1") (pin "72") (pinfunction "RPD0/INT0/RD0_72") (pintype "bidirectional"))
      (node (ref "T42") (pin "P$1") (pinfunction "TP_P$1") (pintype "passive"))
    )
    (net (code "130") (name "unconnected-(CON2-Pad8)") (class "Default")
      (node (ref "CON2") (pin "8") (pinfunction "8_8") (pintype "bidirectional"))
    )
    (net (code "131") (name "unconnected-(IC1-AN8{slash}RPB8{slash}CTED10{slash}RB8-Pad32)") (class "Default")
      (node (ref "IC1") (pin "32") (pinfunction "AN8/RPB8/CTED10/RB8_32") (pintype "bidirectional"))
    )
    (net (code "132") (name "unconnected-(IC1-AN9{slash}RPB9{slash}CTED4{slash}RB9-Pad33)") (class "Default")
      (node (ref "IC1") (pin "33") (pinfunction "AN9/RPB9/CTED4/RB9_33") (pintype "bidirectional"))
    )
    (net (code "133") (name "unconnected-(IC1-AN11{slash}PMA12{slash}RB11-Pad35)") (class "Default")
      (node (ref "IC1") (pin "35") (pinfunction "AN11/PMA12/RB11_35") (pintype "bidirectional"))
    )
    (net (code "134") (name "unconnected-(IC1-AN12{slash}PMA11{slash}RB12-Pad41)") (class "Default")
      (node (ref "IC1") (pin "41") (pinfunction "AN12/PMA11/RB12_41") (pintype "bidirectional"))
    )
    (net (code "135") (name "unconnected-(IC1-AN14{slash}RPB14{slash}PMA1{slash}CTED5{slash}RB14-Pad43)") (class "Default")
      (node (ref "IC1") (pin "43") (pinfunction "AN14/RPB14/PMA1/CTED5/RB14_43") (pintype "bidirectional"))
    )
    (net (code "136") (name "unconnected-(IC1-AN15{slash}RPB15{slash}PMA0{slash}CTED6{slash}{slash}RB15-Pad44)") (class "Default")
      (node (ref "IC1") (pin "44") (pinfunction "AN15/RPB15/PMA0/CTED6//RB15_44") (pintype "bidirectional"))
    )
    (net (code "137") (name "unconnected-(IC1-AN20{slash}PMD2{slash}RE2-Pad98)") (class "Default")
      (node (ref "IC1") (pin "98") (pinfunction "AN20/PMD2/RE2_98") (pintype "bidirectional"))
    )
    (net (code "138") (name "unconnected-(IC1-AN21{slash}PMD4{slash}RE4-Pad100)") (class "Default")
      (node (ref "IC1") (pin "100") (pinfunction "AN21/PMD4/RE4_100") (pintype "bidirectional"))
    )
    (net (code "139") (name "unconnected-(IC1-AN22{slash}RPE5{slash}PMD5{slash}RE5-Pad3)") (class "Default")
      (node (ref "IC1") (pin "3") (pinfunction "AN22/RPE5/PMD5/RE5_3") (pintype "bidirectional"))
    )
    (net (code "140") (name "unconnected-(IC1-AN23{slash}PMD6{slash}RE6-Pad4)") (class "Default")
      (node (ref "IC1") (pin "4") (pinfunction "AN23/PMD6/RE6_4") (pintype "bidirectional"))
    )
    (net (code "141") (name "unconnected-(IC1-AN24{slash}RPD1{slash}RD1-Pad76)") (class "Default")
      (node (ref "IC1") (pin "76") (pinfunction "AN24/RPD1/RD1_76") (pintype "bidirectional"))
    )
    (net (code "142") (name "unconnected-(IC1-AN27{slash}PMD7{slash}RE7-Pad5)") (class "Default")
      (node (ref "IC1") (pin "5") (pinfunction "AN27/PMD7/RE7_5") (pintype "bidirectional"))
    )
    (net (code "143") (name "unconnected-(IC1-CVREFOUT{slash}AN10{slash}RPB10{slash}PMA13{slash}CTED11{slash}RB10-Pad34)") (class "Default")
      (node (ref "IC1") (pin "34") (pinfunction "CVREFOUT/AN10/RPB10/PMA13/CTED11/RB10_34") (pintype "bidirectional"))
    )
    (net (code "144") (name "unconnected-(IC1-PMD0{slash}RE0-Pad93)") (class "Default")
      (node (ref "IC1") (pin "93") (pinfunction "PMD0/RE0_93") (pintype "bidirectional"))
    )
    (net (code "145") (name "unconnected-(IC1-PMD1{slash}RE1-Pad94)") (class "Default")
      (node (ref "IC1") (pin "94") (pinfunction "PMD1/RE1_94") (pintype "bidirectional"))
    )
    (net (code "146") (name "unconnected-(IC1-PMD13{slash}RD13-Pad80)") (class "Default")
      (node (ref "IC1") (pin "80") (pinfunction "PMD13/RD13_80") (pintype "bidirectional"))
    )
    (net (code "147") (name "unconnected-(IC1-RPC1{slash}RC1-Pad6)") (class "Default")
      (node (ref "IC1") (pin "6") (pinfunction "RPC1/RC1_6") (pintype "bidirectional"))
    )
    (net (code "148") (name "unconnected-(IC1-RPC2{slash}RC2-Pad7)") (class "Default")
      (node (ref "IC1") (pin "7") (pinfunction "RPC2/RC2_7") (pintype "bidirectional"))
    )
    (net (code "149") (name "unconnected-(IC1-RPC3{slash}RC3-Pad8)") (class "Default")
      (node (ref "IC1") (pin "8") (pinfunction "RPC3/RC3_8") (pintype "bidirectional"))
    )
    (net (code "150") (name "unconnected-(IC1-RPD4{slash}PMWR{slash}RD4-Pad81)") (class "Default")
      (node (ref "IC1") (pin "81") (pinfunction "RPD4/PMWR/RD4_81") (pintype "bidirectional"))
    )
    (net (code "151") (name "unconnected-(IC1-RPD5{slash}PMRD{slash}RD5-Pad82)") (class "Default")
      (node (ref "IC1") (pin "82") (pinfunction "RPD5/PMRD/RD5_82") (pintype "bidirectional"))
    )
    (net (code "152") (name "unconnected-(IC1-RPD8{slash}RTCC{slash}RD8-Pad68)") (class "Default")
      (node (ref "IC1") (pin "68") (pinfunction "RPD8/RTCC/RD8_68") (pintype "bidirectional"))
    )
    (net (code "153") (name "unconnected-(IC1-RPD9{slash}RD9-Pad69)") (class "Default")
      (node (ref "IC1") (pin "69") (pinfunction "RPD9/RD9_69") (pintype "bidirectional"))
    )
    (net (code "154") (name "unconnected-(IC1-RPD10{slash}SCK1{slash}PMCS2{slash}RD10-Pad70)") (class "Default")
      (node (ref "IC1") (pin "70") (pinfunction "RPD10/SCK1/PMCS2/RD10_70") (pintype "bidirectional"))
    )
    (net (code "155") (name "unconnected-(IC1-RPD11{slash}PMCS1{slash}RD11-Pad71)") (class "Default")
      (node (ref "IC1") (pin "71") (pinfunction "RPD11/PMCS1/RD11_71") (pintype "bidirectional"))
    )
    (net (code "156") (name "unconnected-(IC1-RPD12{slash}PMD12{slash}RD12-Pad79)") (class "Default")
      (node (ref "IC1") (pin "79") (pinfunction "RPD12/PMD12/RD12_79") (pintype "bidirectional"))
    )
    (net (code "157") (name "unconnected-(IC1-RPD14{slash}RD14-Pad47)") (class "Default")
      (node (ref "IC1") (pin "47") (pinfunction "RPD14/RD14_47") (pintype "bidirectional"))
    )
    (net (code "158") (name "unconnected-(IC1-RPD15{slash}RD15-Pad48)") (class "Default")
      (node (ref "IC1") (pin "48") (pinfunction "RPD15/RD15_48") (pintype "bidirectional"))
    )
    (net (code "159") (name "unconnected-(IC1-RPE3{slash}PMD3{slash}RE3-Pad99)") (class "Default")
      (node (ref "IC1") (pin "99") (pinfunction "RPE3/PMD3/RE3_99") (pintype "bidirectional"))
    )
    (net (code "160") (name "unconnected-(IC1-RPF12{slash}RF12-Pad40)") (class "Default")
      (node (ref "IC1") (pin "40") (pinfunction "RPF12/RF12_40") (pintype "bidirectional"))
    )
    (net (code "161") (name "unconnected-(IC1-RPF13{slash}RF13-Pad39)") (class "Default")
      (node (ref "IC1") (pin "39") (pinfunction "RPF13/RF13_39") (pintype "bidirectional"))
    )
    (net (code "162") (name "unconnected-(IC1-RPG0{slash}PMD8{slash}RG0-Pad90)") (class "Default")
      (node (ref "IC1") (pin "90") (pinfunction "RPG0/PMD8/RG0_90") (pintype "bidirectional"))
    )
    (net (code "163") (name "unconnected-(IC1-SCL2{slash}RA2-Pad58)") (class "Default")
      (node (ref "IC1") (pin "58") (pinfunction "SCL2/RA2_58") (pintype "bidirectional"))
    )
    (net (code "164") (name "unconnected-(IC1-SDA2{slash}RA3-Pad59)") (class "Default")
      (node (ref "IC1") (pin "59") (pinfunction "SDA2/RA3_59") (pintype "bidirectional"))
    )
    (net (code "165") (name "unconnected-(IC1-TCK{slash}CTED2{slash}RA1-Pad38)") (class "Default")
      (node (ref "IC1") (pin "38") (pinfunction "TCK/CTED2/RA1_38") (pintype "bidirectional"))
    )
    (net (code "166") (name "unconnected-(IC1-TDI{slash}CTED9{slash}RA4-Pad60)") (class "Default")
      (node (ref "IC1") (pin "60") (pinfunction "TDI/CTED9/RA4_60") (pintype "bidirectional"))
    )
    (net (code "167") (name "unconnected-(IC1-TDO{slash}RA5-Pad61)") (class "Default")
      (node (ref "IC1") (pin "61") (pinfunction "TDO/RA5_61") (pintype "bidirectional"))
    )
    (net (code "168") (name "unconnected-(IC1-TMS{slash}CTED1{slash}RA0-Pad17)") (class "Default")
      (node (ref "IC1") (pin "17") (pinfunction "TMS/CTED1/RA0_17") (pintype "bidirectional"))
    )
    (net (code "169") (name "unconnected-(IC1-TRD0{slash}RG13-Pad97)") (class "Default")
      (node (ref "IC1") (pin "97") (pinfunction "TRD0/RG13_97") (pintype "bidirectional"))
    )
    (net (code "170") (name "unconnected-(IC1-TRD2{slash}RG14-Pad95)") (class "Default")
      (node (ref "IC1") (pin "95") (pinfunction "TRD2/RG14_95") (pintype "bidirectional"))
    )
    (net (code "171") (name "unconnected-(IC3-PG-Pad9)") (class "Default")
      (node (ref "IC3") (pin "9") (pinfunction "PG_9") (pintype "bidirectional"))
    )
    (net (code "172") (name "unconnected-(Q1A-D-Pad6)") (class "Default")
      (node (ref "Q1") (pin "6") (pinfunction "D_6") (pintype "passive"))
    )
    (net (code "173") (name "unconnected-(Q1A-D1-PadP1)") (class "Default")
      (node (ref "Q1") (pin "P1") (pinfunction "D1_P1") (pintype "passive"))
    )
    (net (code "174") (name "unconnected-(Q1A-G-Pad2)") (class "Default")
      (node (ref "Q1") (pin "2") (pinfunction "G_2") (pintype "passive"))
    )
    (net (code "175") (name "unconnected-(Q1A-S-Pad1)") (class "Default")
      (node (ref "Q1") (pin "1") (pinfunction "S_1") (pintype "passive"))
    )
    (net (code "176") (name "unconnected-(Q2A-D-Pad6)") (class "Default")
      (node (ref "Q2") (pin "6") (pinfunction "D_6") (pintype "passive"))
    )
    (net (code "177") (name "unconnected-(Q2A-D1-PadP1)") (class "Default")
      (node (ref "Q2") (pin "P1") (pinfunction "D1_P1") (pintype "passive"))
    )
    (net (code "178") (name "unconnected-(Q2A-G-Pad2)") (class "Default")
      (node (ref "Q2") (pin "2") (pinfunction "G_2") (pintype "passive"))
    )
    (net (code "179") (name "unconnected-(Q2A-S-Pad1)") (class "Default")
      (node (ref "Q2") (pin "1") (pinfunction "S_1") (pintype "passive"))
    )
    (net (code "180") (name "unconnected-(Q6B-D-Pad3)") (class "Default")
      (node (ref "Q6") (pin "3") (pinfunction "D_3") (pintype "passive"))
    )
    (net (code "181") (name "unconnected-(Q6B-G-Pad5)") (class "Default")
      (node (ref "Q6") (pin "5") (pinfunction "G_5") (pintype "passive"))
    )
    (net (code "182") (name "unconnected-(Q6B-S-Pad4)") (class "Default")
      (node (ref "Q6") (pin "4") (pinfunction "S_4") (pintype "passive"))
    )
    (net (code "183") (name "{slash}3.3V1PWRON") (class "Default")
      (node (ref "IC1") (pin "21") (pinfunction "AN4/C1INB/USBOEN/RB4_21") (pintype "bidirectional"))
      (node (ref "O44") (pin "P$1") (pinfunction "TP_P$1") (pintype "passive"))
      (node (ref "R24") (pin "2") (pinfunction "2_2") (pintype "passive"))
      (node (ref "T32") (pin "P$1") (pinfunction "TP_P$1") (pintype "passive"))
    )
    (net (code "184") (name "{slash}3.3V2PWRON") (class "Default")
      (node (ref "IC1") (pin "96") (pinfunction "TRD1/RG12_96") (pintype "bidirectional"))
      (node (ref "O23") (pin "P$1") (pinfunction "TP_P$1") (pintype "passive"))
      (node (ref "R75") (pin "2") (pinfunction "2_2") (pintype "passive"))
      (node (ref "T33") (pin "P$1") (pinfunction "TP_P$1") (pintype "passive"))
    )
    (net (code "185") (name "{slash}FMEM1-CS") (class "Default")
      (node (ref "IC1") (pin "11") (pinfunction "AN17/C1INC/RPG7/PMA4/RG7_11") (pintype "bidirectional"))
      (node (ref "IC9") (pin "1") (pinfunction "/S_1") (pintype "input"))
      (node (ref "O6") (pin "P$1") (pinfunction "TP_P$1") (pintype "passive"))
      (node (ref "R25") (pin "1") (pinfunction "1_1") (pintype "passive"))
      (node (ref "T27") (pin "P$1") (pinfunction "TP_P$1") (pintype "passive"))
    )
    (net (code "186") (name "{slash}MCLR") (class "Default")
      (node (ref "IC1") (pin "13") (pinfunction "~{MCLR}_13") (pintype "input"))
      (node (ref "J17") (pin "1") (pinfunction "1_1") (pintype "passive"))
      (node (ref "R90") (pin "2") (pinfunction "2_2") (pintype "passive"))
    )
  )
)
